# SCH_16b_ADC_DAC__2022-10-03.net
KiCad netlist of a schematic drawn in EasyEDA
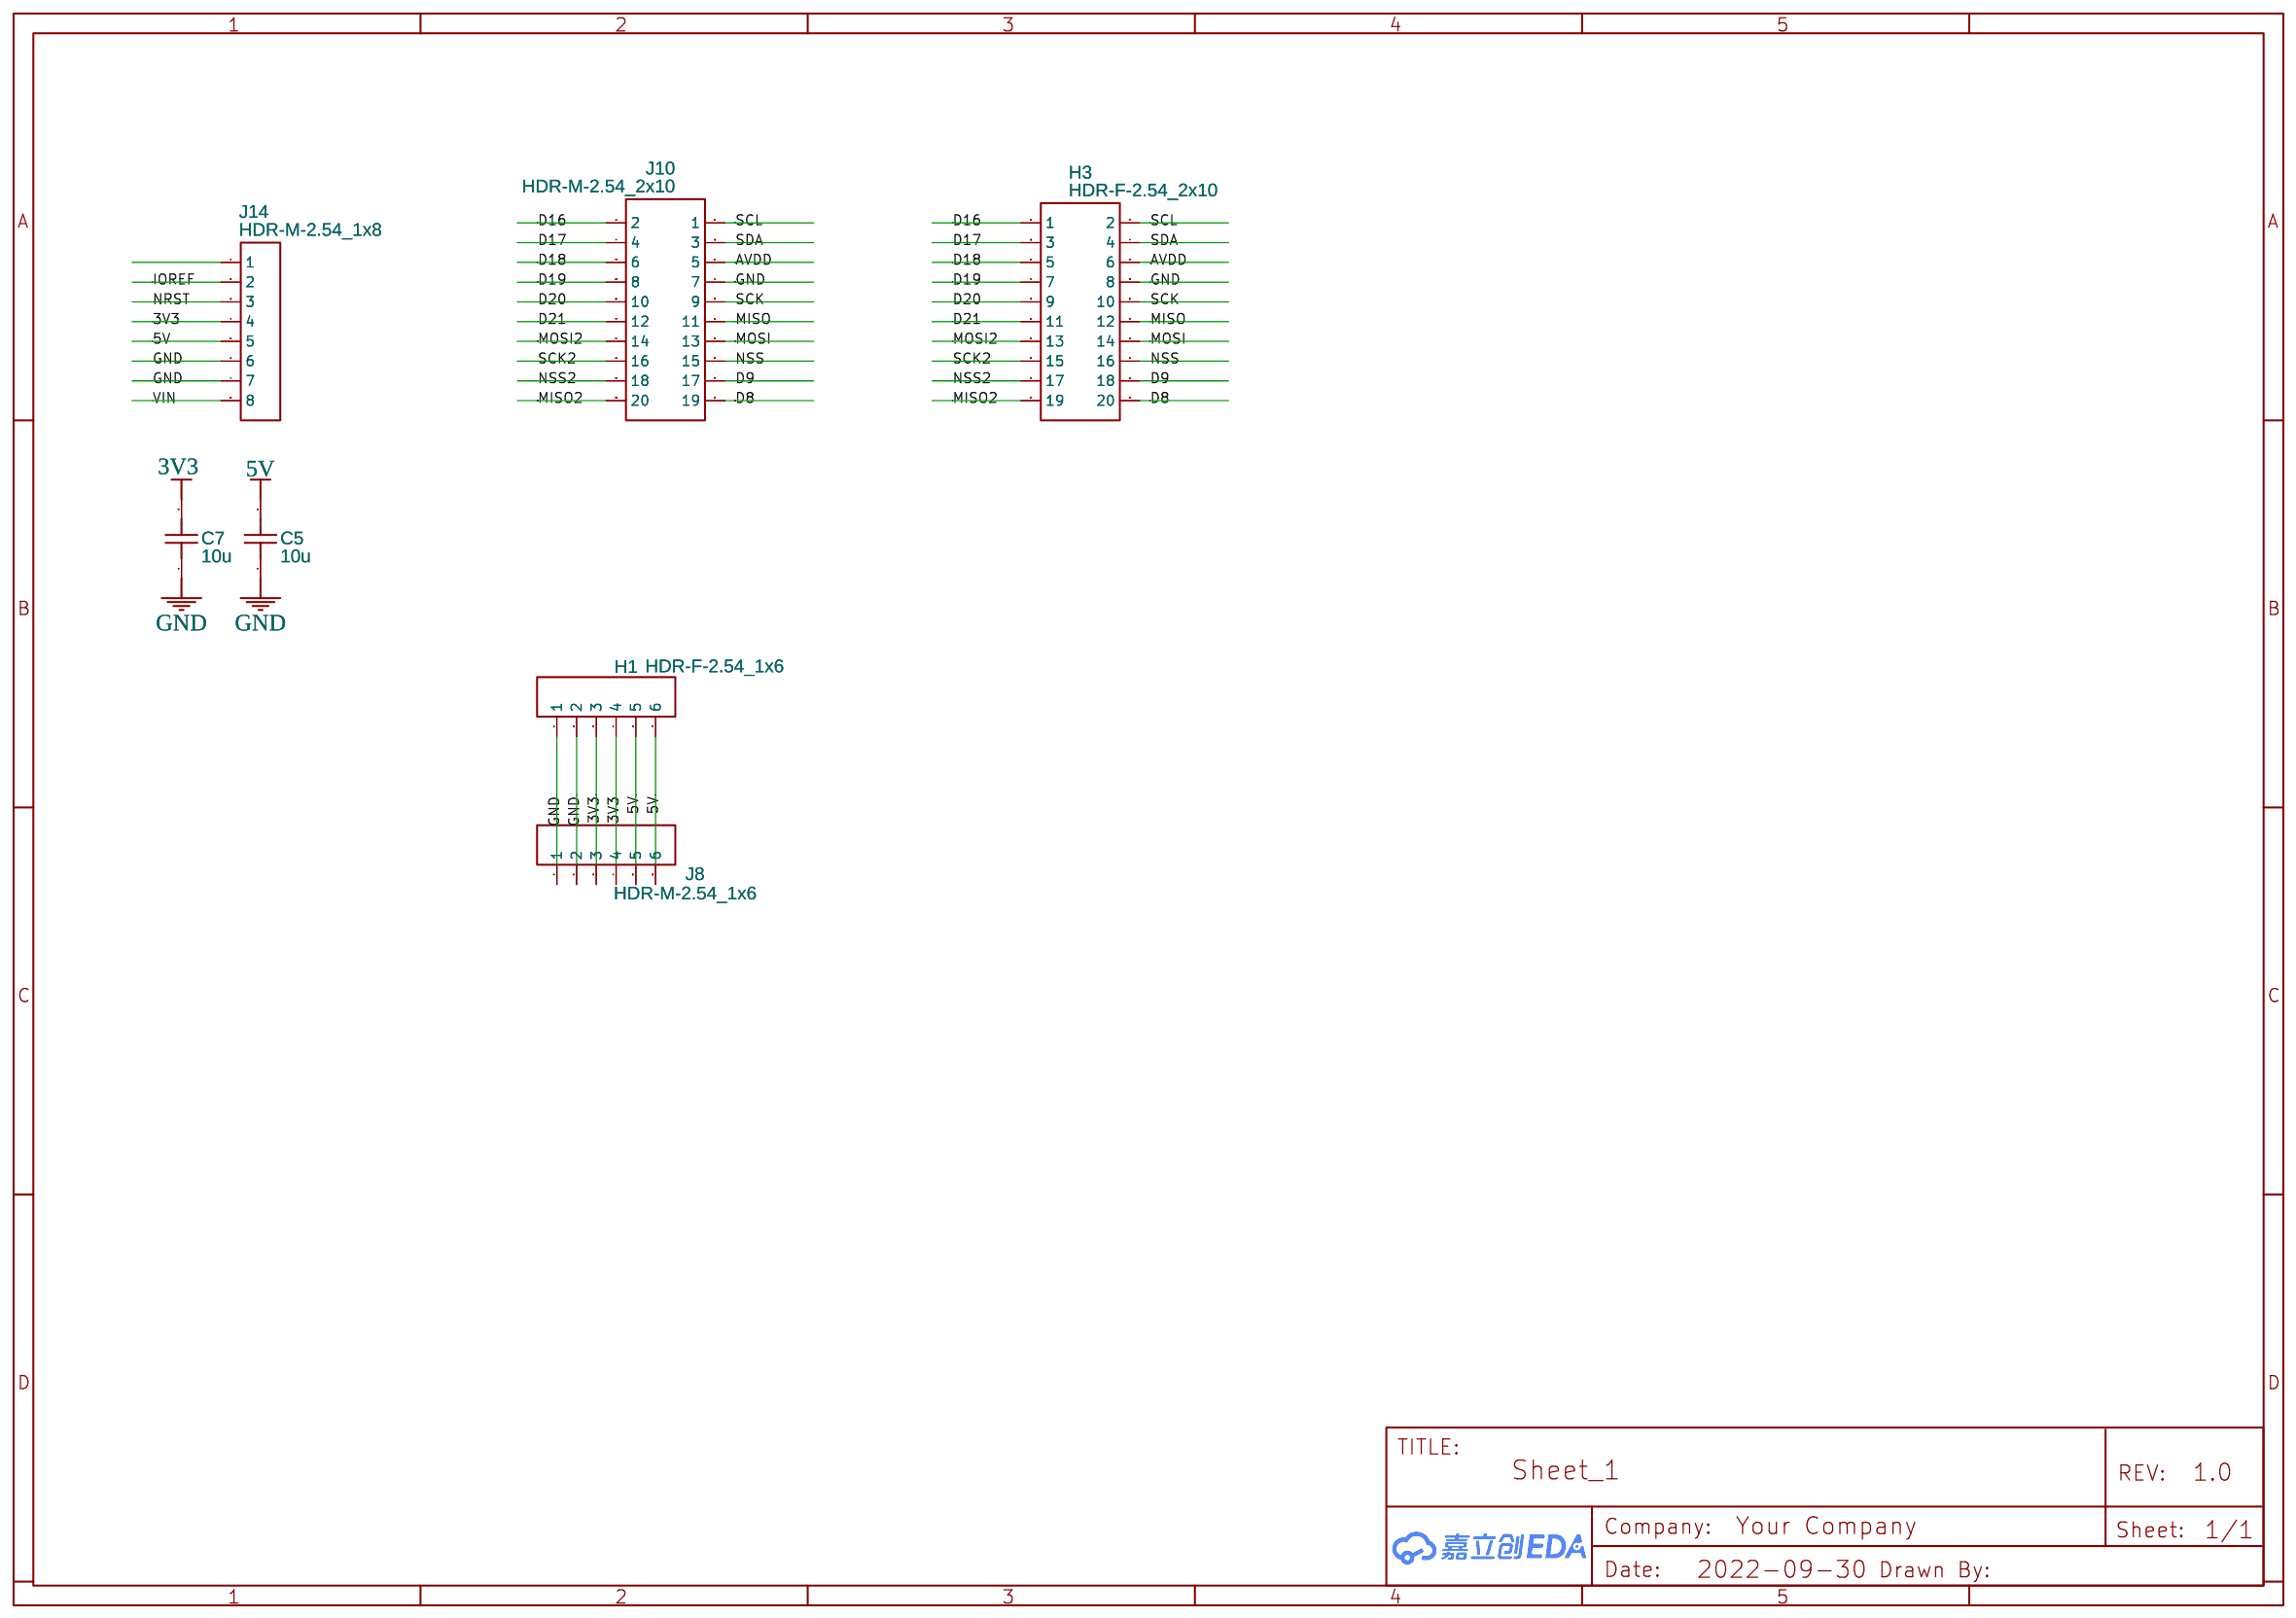
[diagram p0: 连接器]
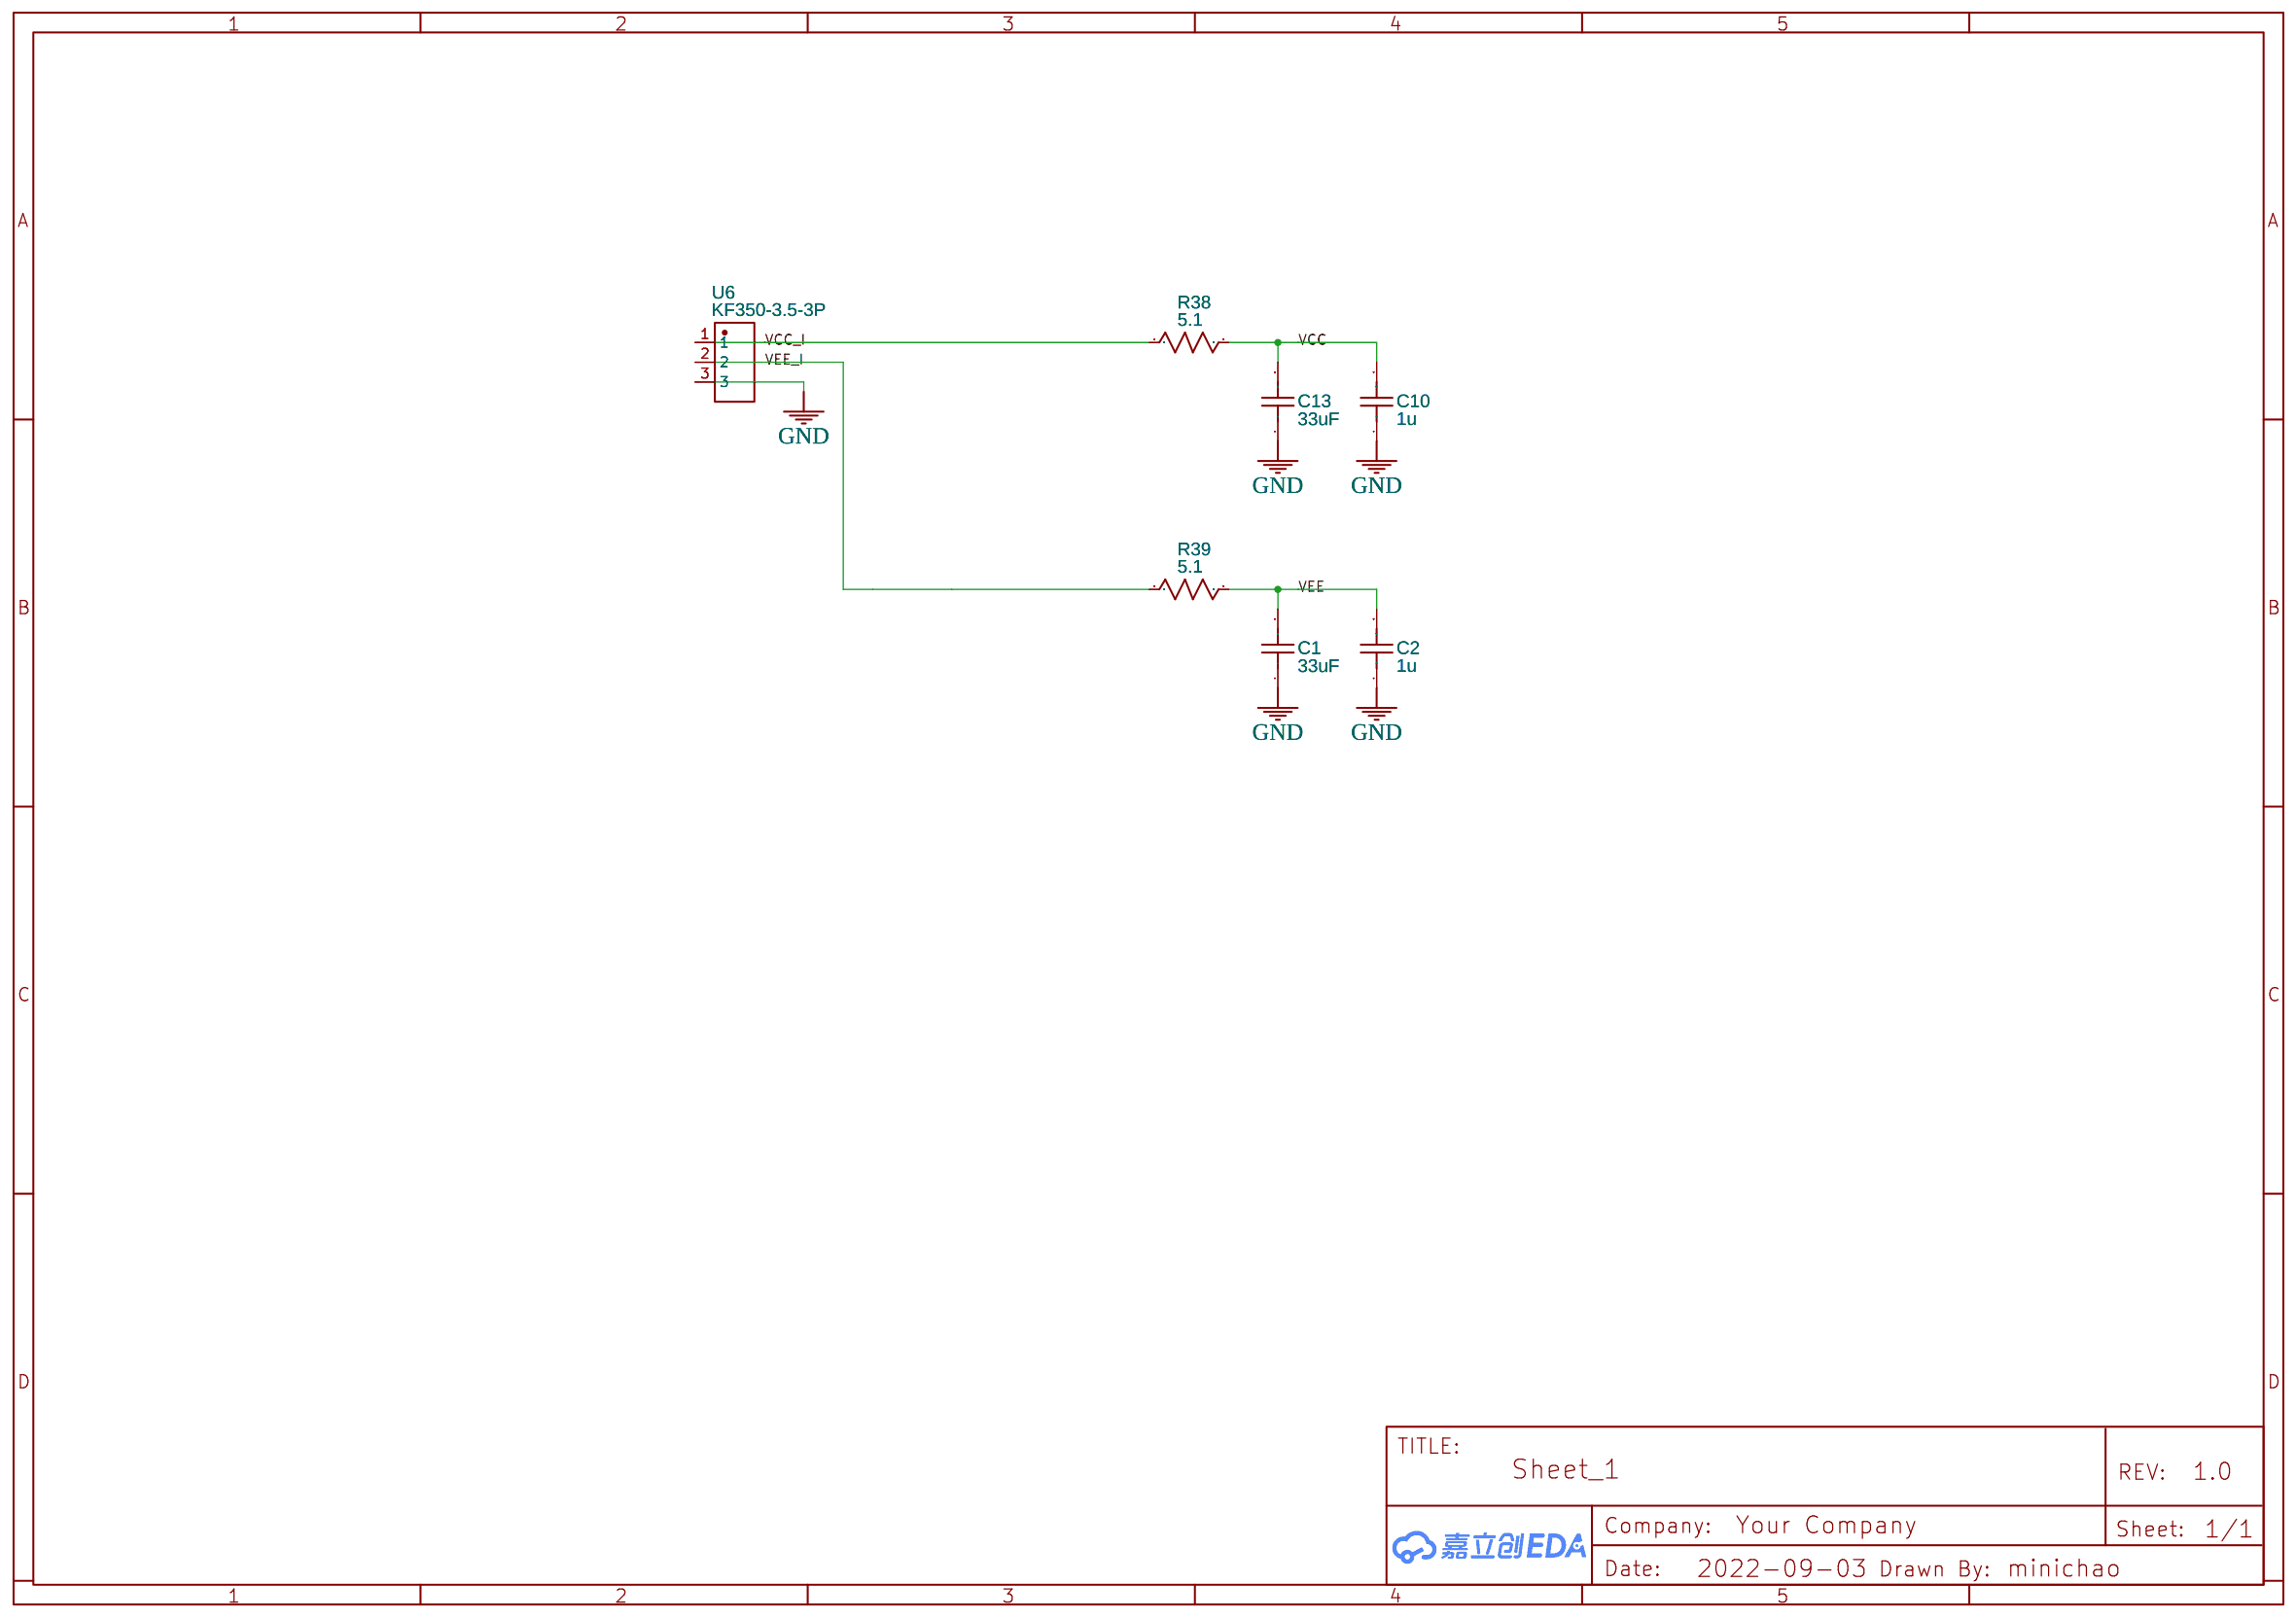
[diagram p1: 电源]
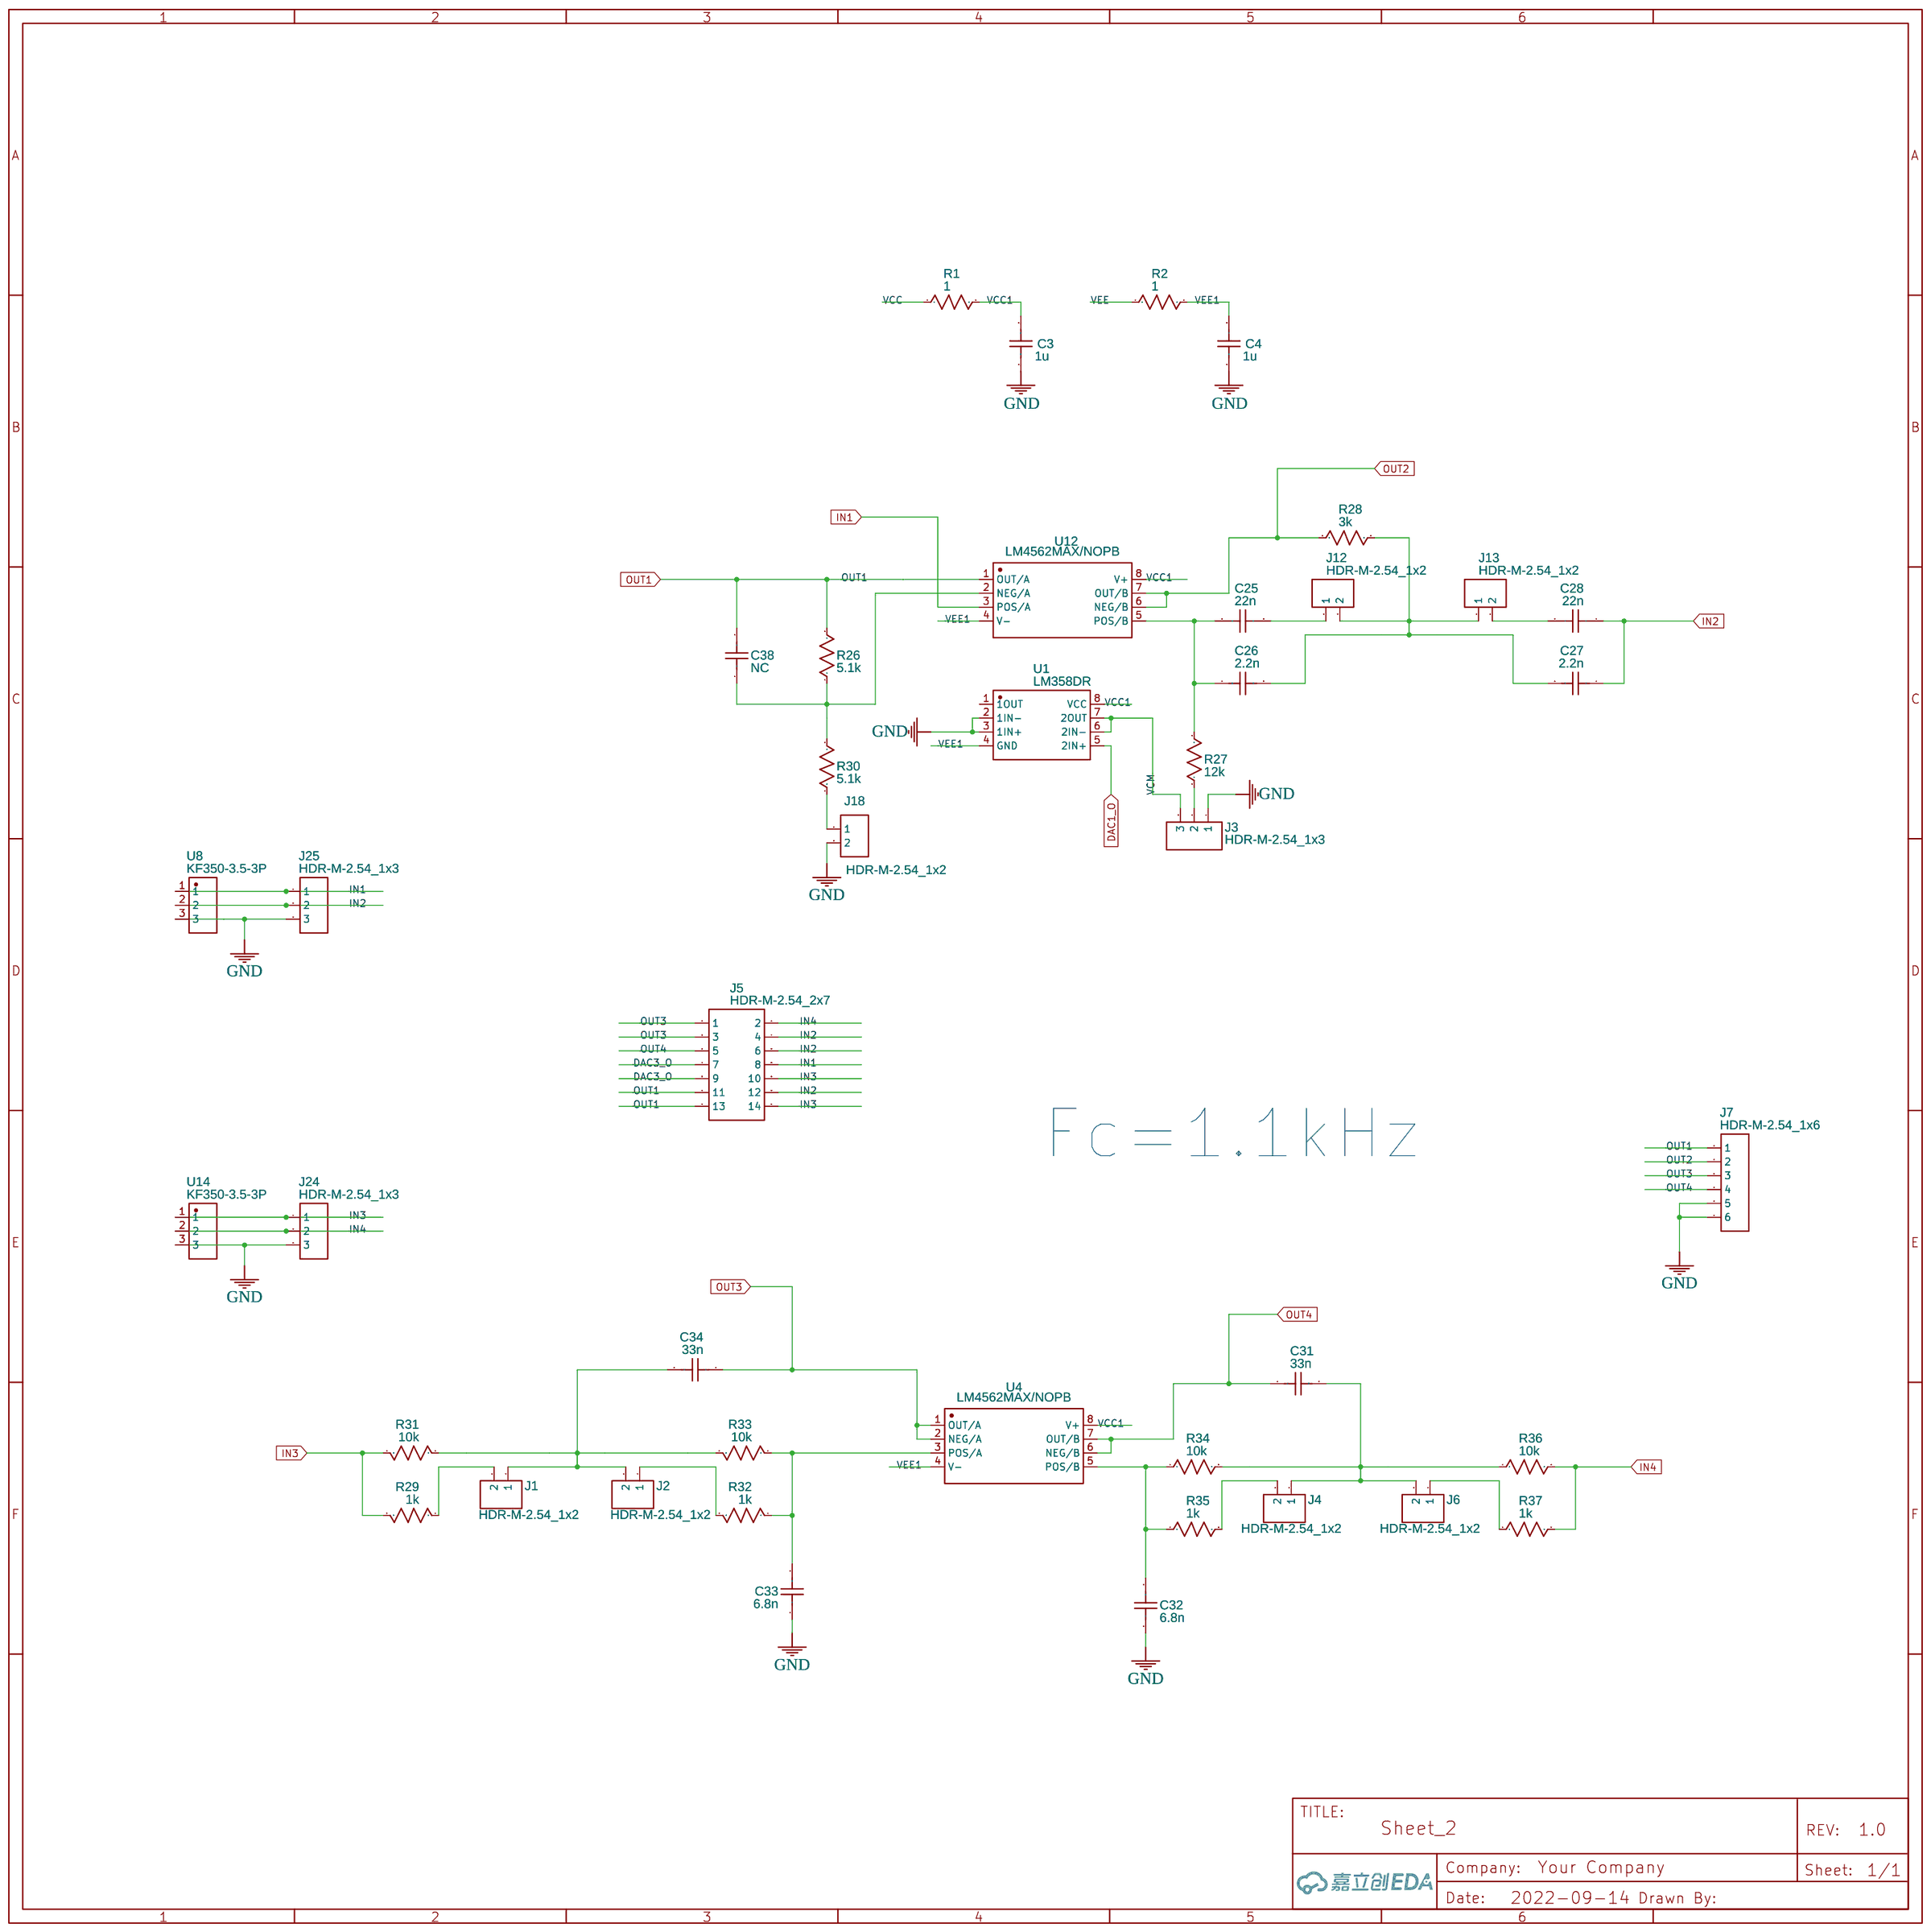
[diagram p2: 有源滤波器]
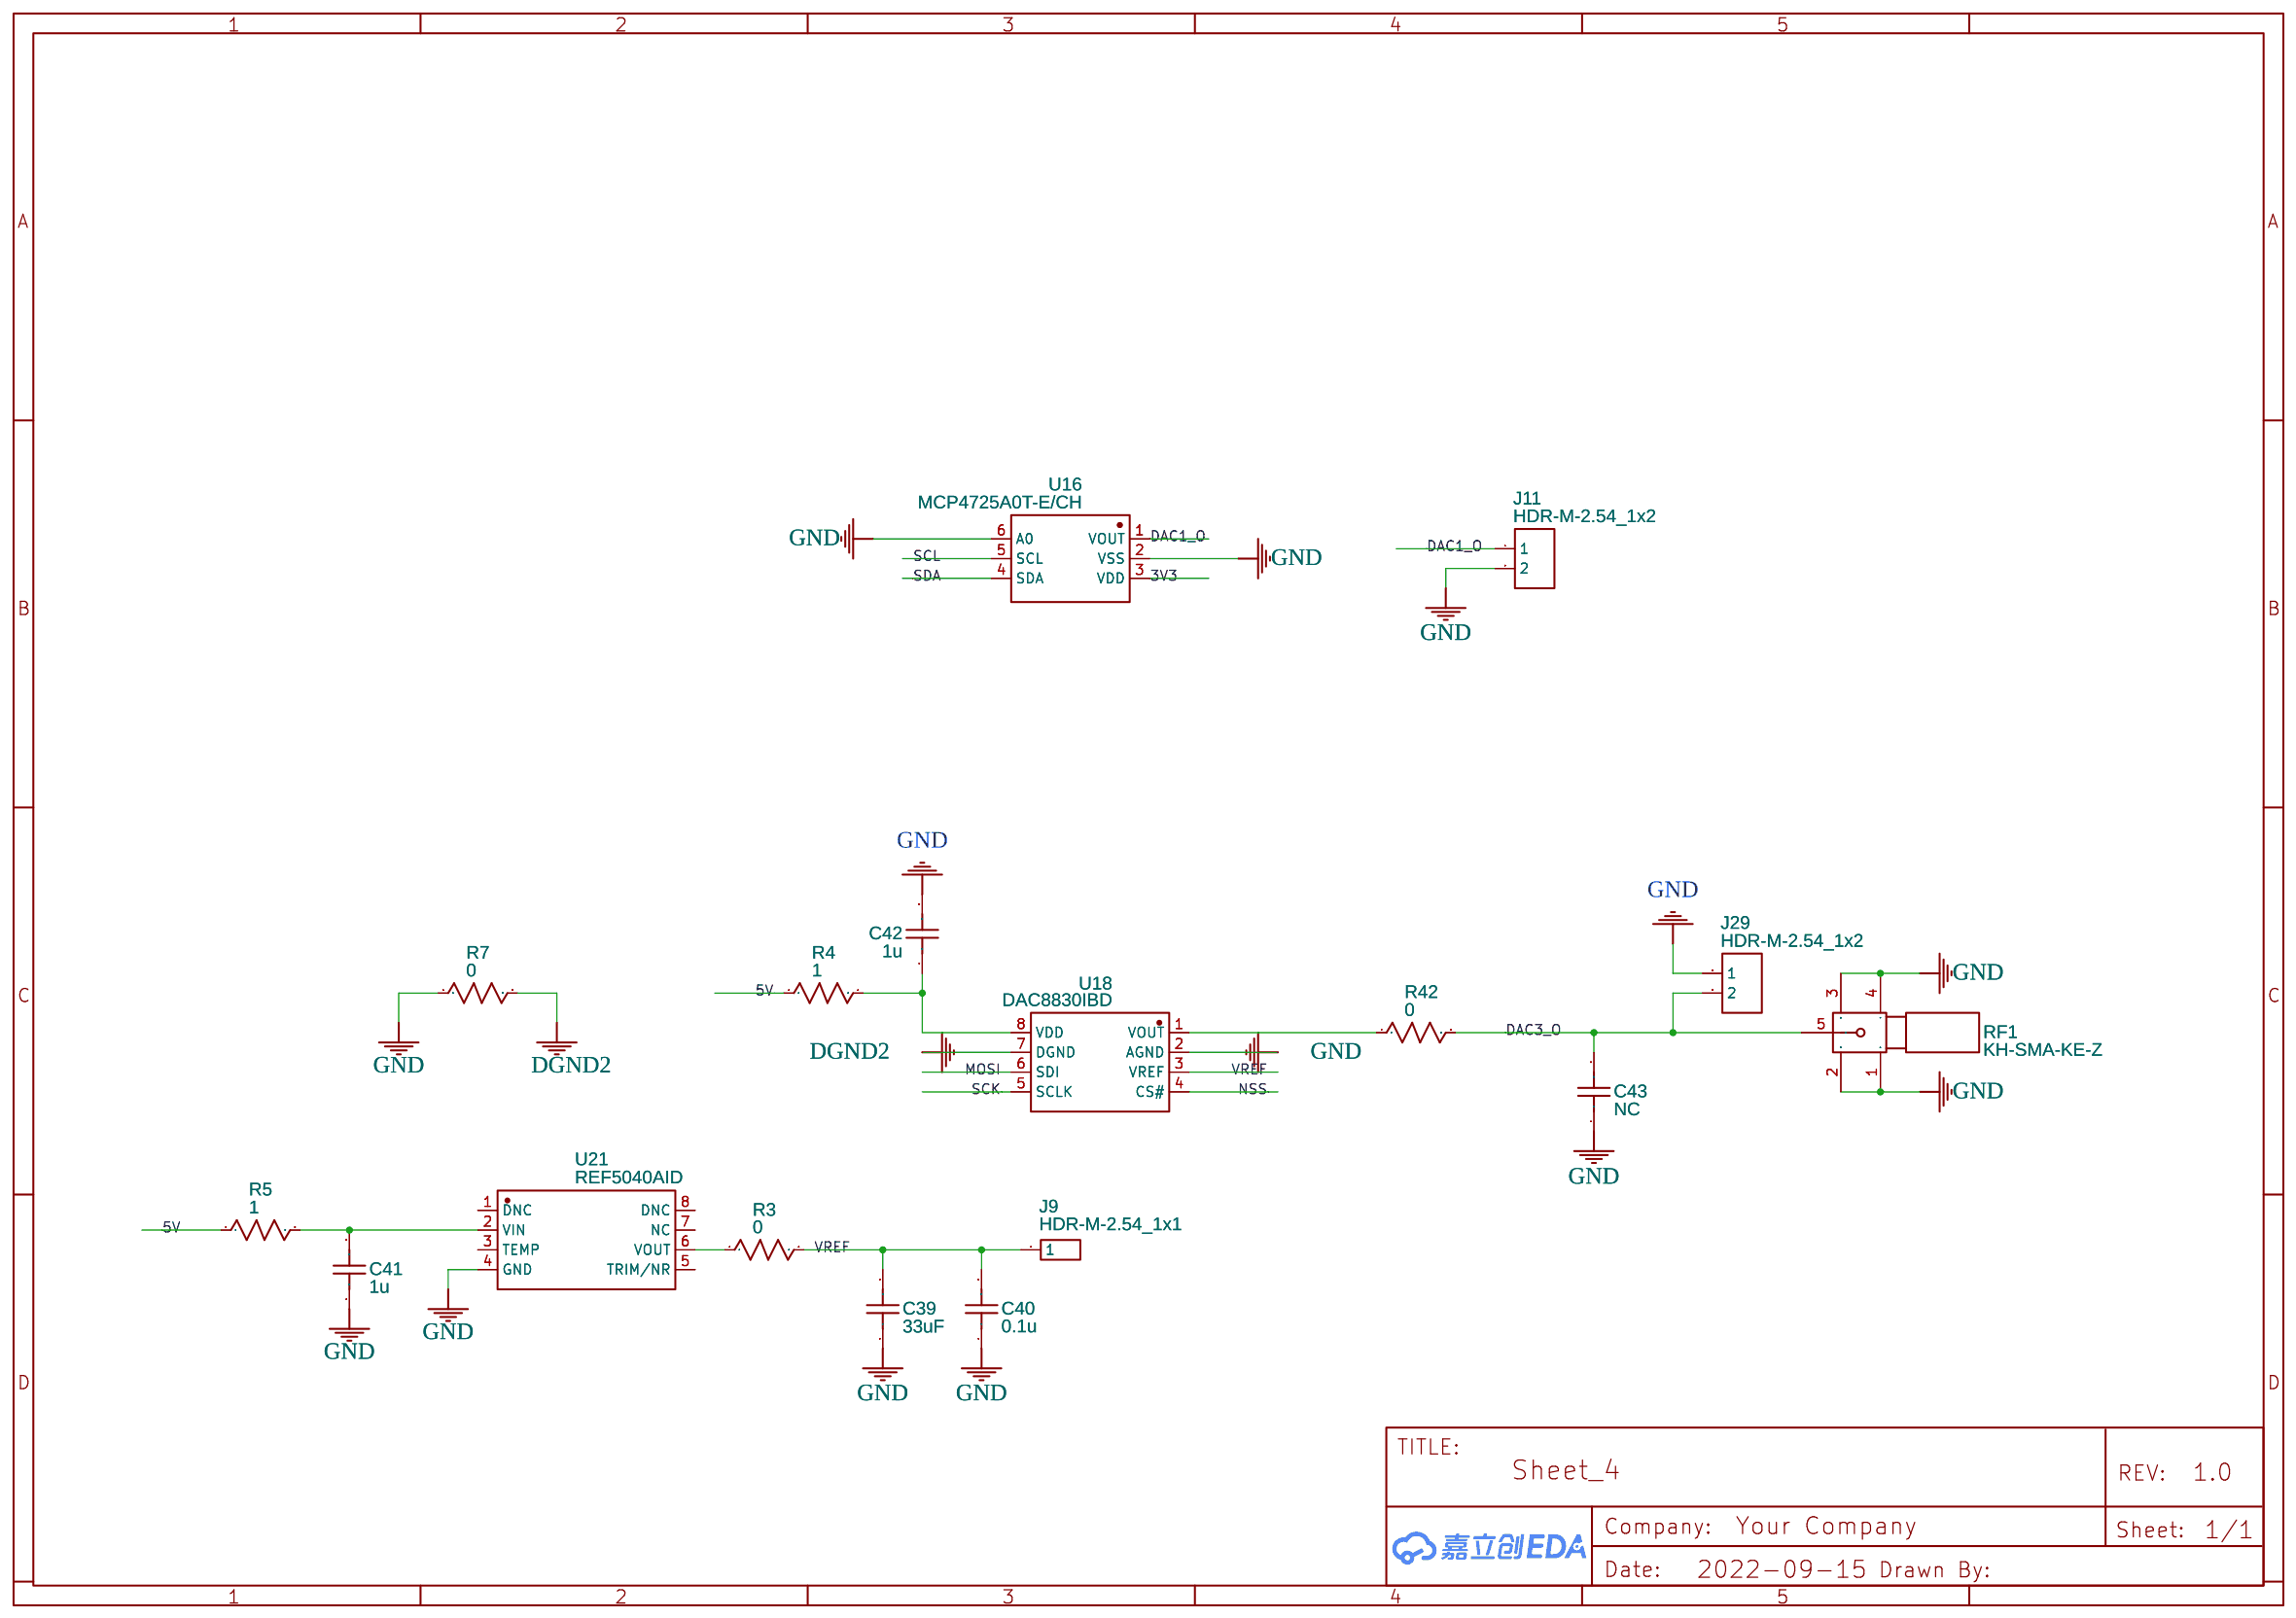
[diagram p3: dac与逻辑电路]
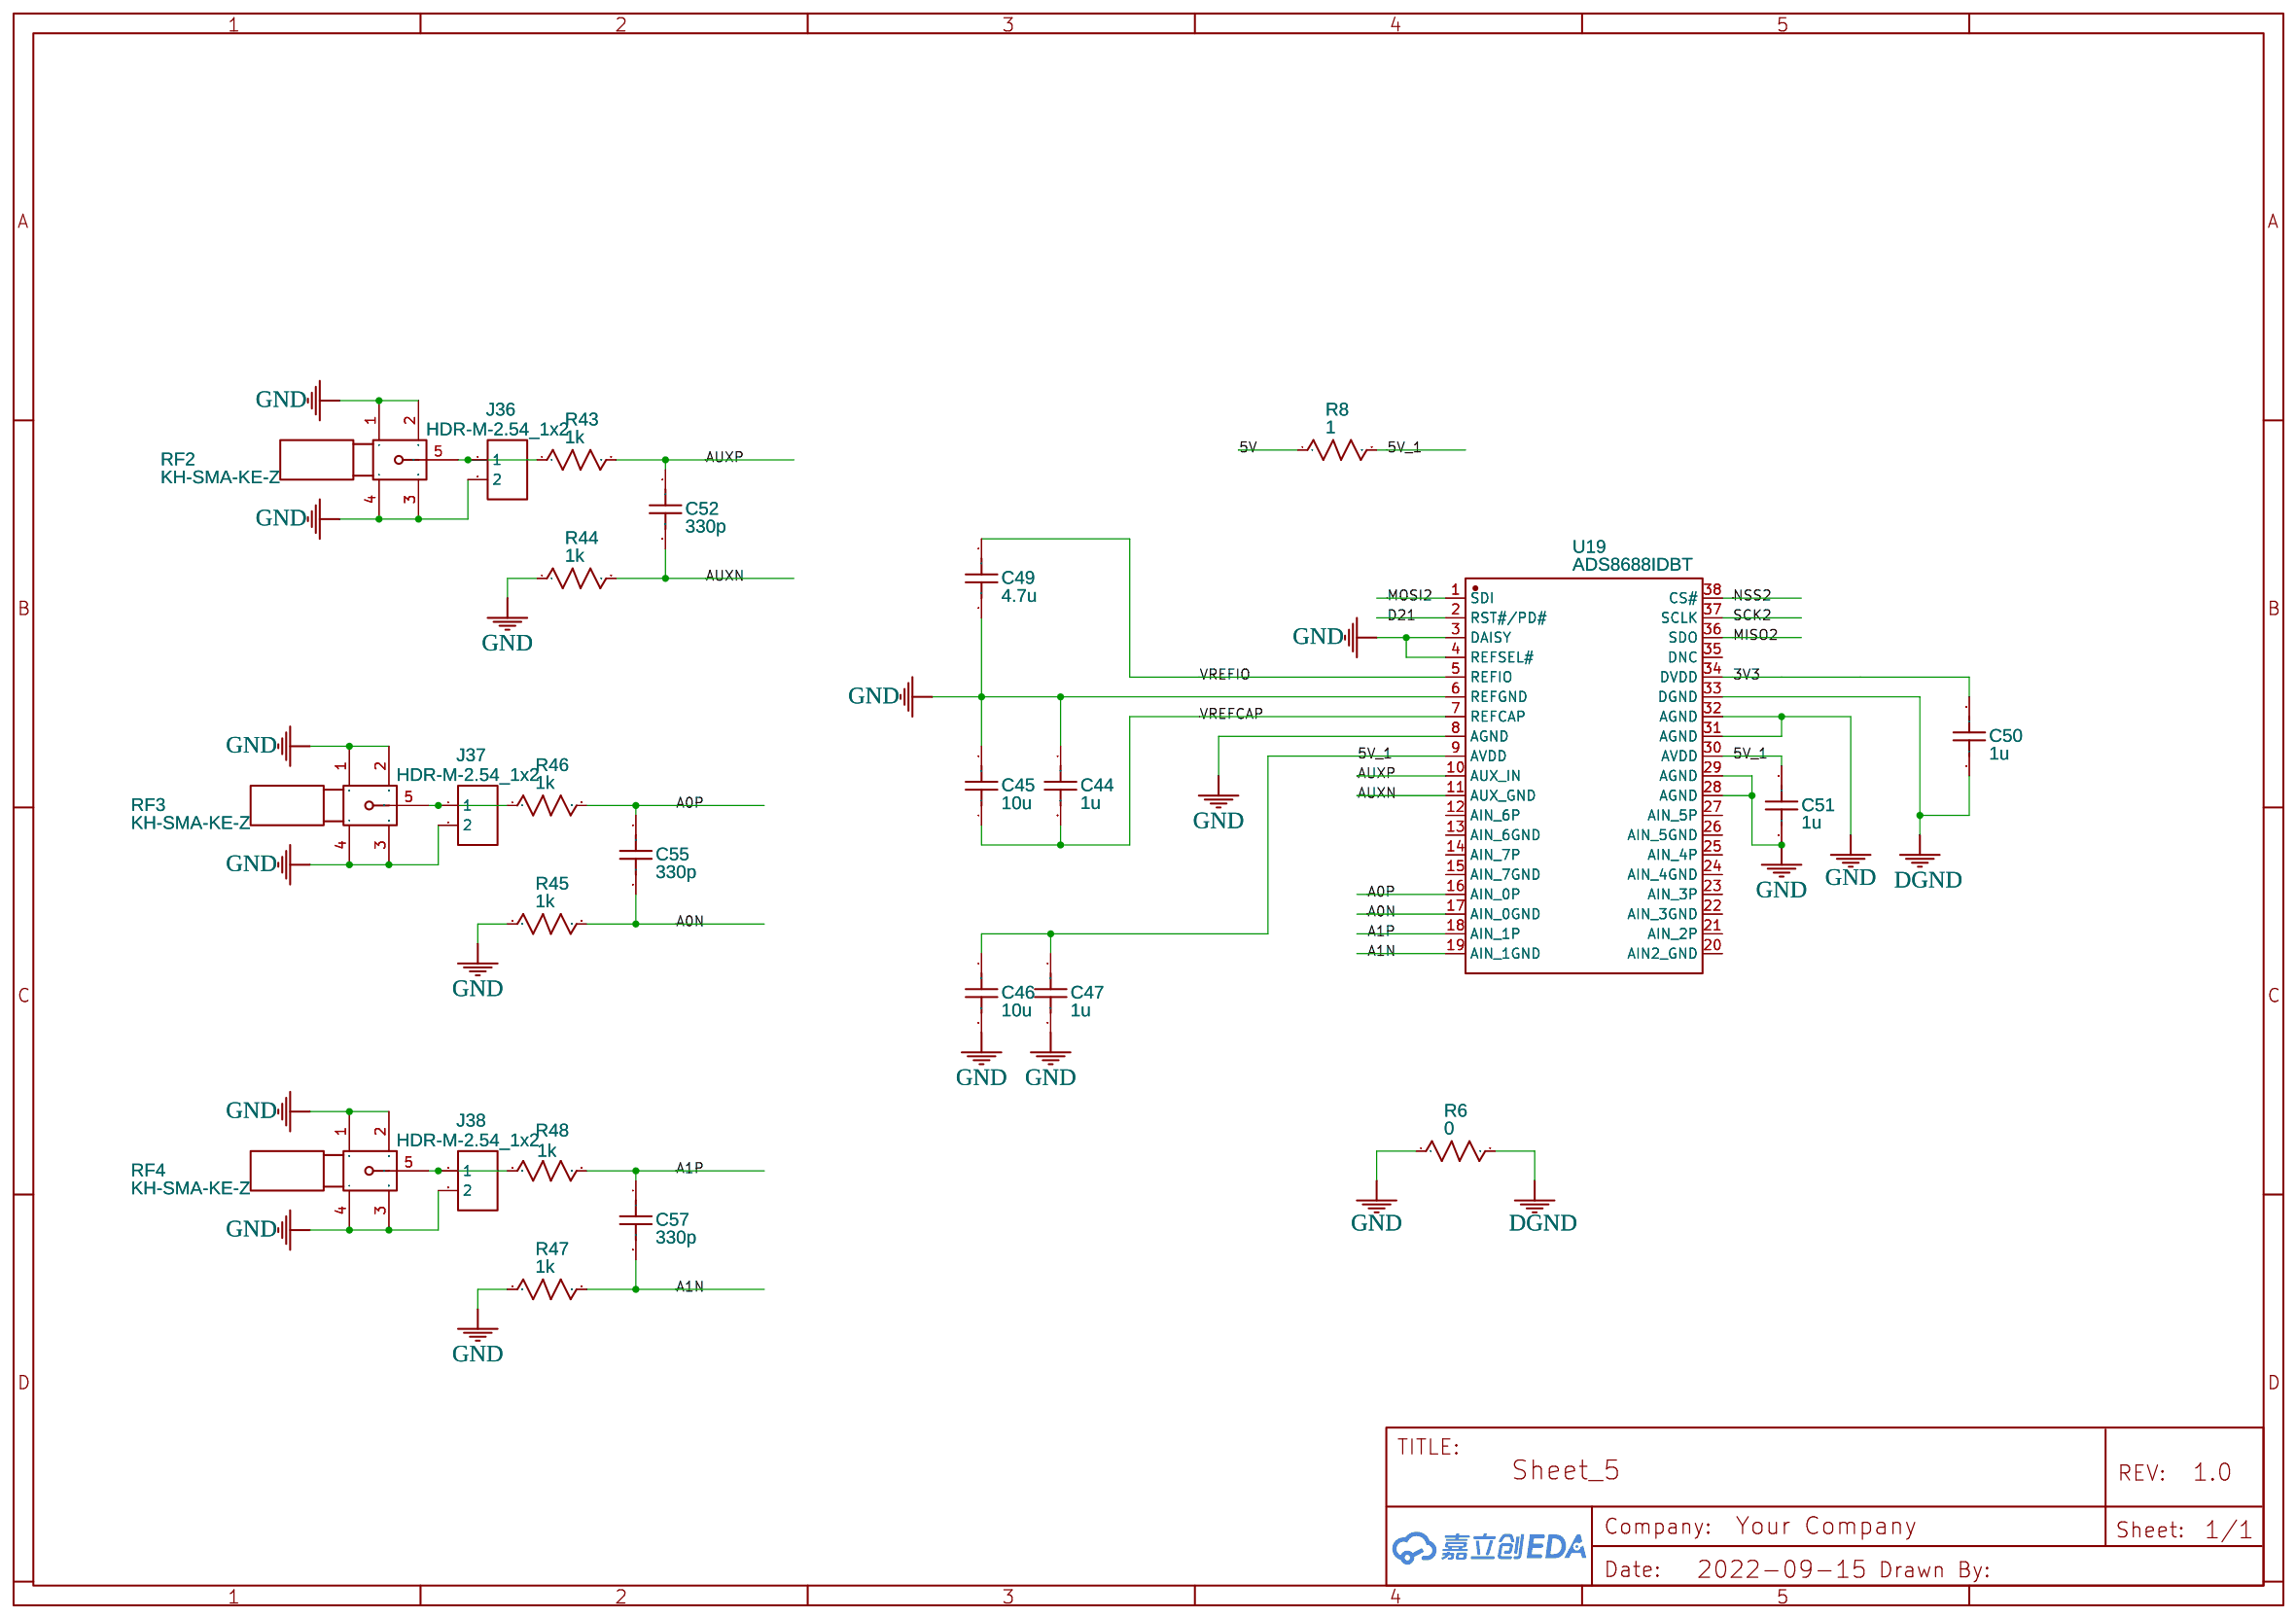
[diagram p4: adc]

(export (version "E")
  (design (tool "Eeschema 10.0.6"))
  (components
    (comp (ref "C5")
      (value "10u")
      (fields
        (field (name "BOM_Manufacturer Part") "0805B105M500NT")
        (field (name "BOM_Supplier Part") "C2913555")
      )
      (libsource (lib "") (part "C_0805_US"))
    )
    (comp (ref "C7")
      (value "10u")
      (fields
        (field (name "BOM_Manufacturer Part") "0805B105M500NT")
        (field (name "BOM_Supplier Part") "C2913555")
      )
      (libsource (lib "") (part "C_0805_US"))
    )
    (comp (ref "H1")
      (value "HDR-F-2.54_1x6")
      (fields (field (name "BOM_Supplier Part") "C40877"))
      (libsource (lib "") (part "HDR-F-2.54_1x6"))
    )
    (comp (ref "H3")
      (value "HDR-F-2.54_2x10")
      (fields (field (name "BOM_Supplier Part") "C30867"))
      (libsource (lib "") (part "HDR-F-2.54_2x10"))
    )
    (comp (ref "J8")
      (value "HDR-M-2.54_1x6")
      (fields (field (name "BOM_Supplier Part") "C190819"))
      (libsource (lib "") (part "HDR-M-2.54_1x6"))
    )
    (comp (ref "J10")
      (value "HDR-M-2.54_2x10")
      (fields (field (name "BOM_Supplier Part") "C124359"))
      (libsource (lib "") (part "HDR-M-2.54_2x10"))
    )
    (comp (ref "J14")
      (value "HDR-M-2.54_1x8")
      (fields (field (name "BOM_Supplier Part") "C190820"))
      (libsource (lib "") (part "HDR-M-2.54_1x8"))
    )
    (comp (ref "C1")
      (value "33uF")
      (fields
        (field (name "BOM_Manufacturer Part") "C4532X5R1C336MT000N")
        (field (name "BOM_Supplier Part") "C338113")
      )
      (libsource (lib "") (part "C4532X5R1C336MT000N"))
    )
    (comp (ref "C2") (value "1u") (libsource (lib "") (part "C_0805_US")))
    (comp (ref "C10") (value "1u") (libsource (lib "") (part "C_0805_US")))
    (comp (ref "C13")
      (value "33uF")
      (fields
        (field (name "BOM_Manufacturer Part") "C4532X5R1C336MT000N")
        (field (name "BOM_Supplier Part") "C338113")
      )
      (libsource (lib "") (part "C4532X5R1C336MT000N"))
    )
    (comp (ref "R38") (value "5.1") (libsource (lib "") (part "R_0805_US")))
    (comp (ref "R39") (value "5.1") (libsource (lib "") (part "R_0805_US")))
    (comp (ref "U6")
      (value "KF350-3.5-3P")
      (fields (field (name "BOM_Supplier Part") "C474893"))
      (libsource (lib "") (part "KF350-3.5-3P"))
    )
    (comp (ref "C3") (value "1u") (libsource (lib "") (part "C_0805_US_2")))
    (comp (ref "C4") (value "1u") (libsource (lib "") (part "C_0805_US_2")))
    (comp (ref "C25") (value "22n") (libsource (lib "") (part "C_0805_US_3")))
    (comp (ref "C26") (value "2.2n") (libsource (lib "") (part "C_0805_US_3")))
    (comp (ref "C27") (value "2.2n") (libsource (lib "") (part "C_0805_US")))
    (comp (ref "C28") (value "22n") (libsource (lib "") (part "C_0805_US")))
    (comp (ref "C31") (value "33n") (libsource (lib "") (part "C_0805_US_3")))
    (comp (ref "C32") (value "6.8n") (libsource (lib "") (part "C_0805_US_2")))
    (comp (ref "C33") (value "6.8n") (libsource (lib "") (part "C_0805_US_1")))
    (comp (ref "C34") (value "33n") (libsource (lib "") (part "C_0805_US")))
    (comp (ref "C38") (value "NC") (libsource (lib "") (part "C_0805_US_2")))
    (comp (ref "J1")
      (value "HDR-M-2.54_1x2")
      (fields (field (name "BOM_Supplier Part") "C124375"))
      (libsource (lib "") (part "HDR-M-2.54_1x2_1"))
    )
    (comp (ref "J2")
      (value "HDR-M-2.54_1x2")
      (fields (field (name "BOM_Supplier Part") "C124375"))
      (libsource (lib "") (part "HDR-M-2.54_1x2_1"))
    )
    (comp (ref "J3")
      (value "HDR-M-2.54_1x3")
      (fields (field (name "BOM_Supplier Part") "C180248"))
      (libsource (lib "") (part "HDR-M-2.54_1x3"))
    )
    (comp (ref "J4")
      (value "HDR-M-2.54_1x2")
      (fields (field (name "BOM_Supplier Part") "C124375"))
      (libsource (lib "") (part "HDR-M-2.54_1x2_1"))
    )
    (comp (ref "J5")
      (value "HDR-M-2.54_2x7")
      (fields (field (name "BOM_Supplier Part") "C71397"))
      (libsource (lib "") (part "HDR-M-2.54_2x7"))
    )
    (comp (ref "J6")
      (value "HDR-M-2.54_1x2")
      (fields (field (name "BOM_Supplier Part") "C124375"))
      (libsource (lib "") (part "HDR-M-2.54_1x2_1"))
    )
    (comp (ref "J7")
      (value "HDR-M-2.54_1x6")
      (fields (field (name "BOM_Supplier Part") "C190819"))
      (libsource (lib "") (part "HDR-M-2.54_1x6"))
    )
    (comp (ref "J12")
      (value "HDR-M-2.54_1x2")
      (fields (field (name "BOM_Supplier Part") "C124375"))
      (libsource (lib "") (part "HDR-M-2.54_1x2"))
    )
    (comp (ref "J13")
      (value "HDR-M-2.54_1x2")
      (fields (field (name "BOM_Supplier Part") "C124375"))
      (libsource (lib "") (part "HDR-M-2.54_1x2"))
    )
    (comp (ref "J18")
      (value "HDR-M-2.54_1x2")
      (fields (field (name "BOM_Supplier Part") "C124375"))
      (libsource (lib "") (part "HDR-M-2.54_1x2_2"))
    )
    (comp (ref "J24")
      (value "HDR-M-2.54_1x3")
      (fields (field (name "BOM_Supplier Part") "C180248"))
      (libsource (lib "") (part "HDR-M-2.54_1x3_1"))
    )
    (comp (ref "J25")
      (value "HDR-M-2.54_1x3")
      (fields (field (name "BOM_Supplier Part") "C180248"))
      (libsource (lib "") (part "HDR-M-2.54_1x3_1"))
    )
    (comp (ref "R1") (value "1") (libsource (lib "") (part "R_0805_US_1")))
    (comp (ref "R2") (value "1") (libsource (lib "") (part "R_0805_US_1")))
    (comp (ref "R26") (value "5.1k") (libsource (lib "") (part "R_0805_US")))
    (comp (ref "R27") (value "12k") (libsource (lib "") (part "R_0805_US")))
    (comp (ref "R28") (value "3k") (libsource (lib "") (part "R_0805_US_1")))
    (comp (ref "R29") (value "1k") (libsource (lib "") (part "R_0805_US_2")))
    (comp (ref "R30") (value "5.1k") (libsource (lib "") (part "R_0805_US")))
    (comp (ref "R31") (value "10k") (libsource (lib "") (part "R_0805_US_2")))
    (comp (ref "R32") (value "1k") (libsource (lib "") (part "R_0805_US_2")))
    (comp (ref "R33") (value "10k") (libsource (lib "") (part "R_0805_US_2")))
    (comp (ref "R34") (value "10k") (libsource (lib "") (part "R_0805_US_1")))
    (comp (ref "R35") (value "1k") (libsource (lib "") (part "R_0805_US_1")))
    (comp (ref "R36") (value "10k") (libsource (lib "") (part "R_0805_US_1")))
    (comp (ref "R37") (value "1k") (libsource (lib "") (part "R_0805_US_1")))
    (comp (ref "U1")
      (value "LM358DR")
      (fields (field (name "BOM_Supplier Part") "C5423"))
      (libsource (lib "") (part "LM358DR"))
    )
    (comp (ref "U4")
      (value "LM4562MAX/NOPB")
      (fields (field (name "BOM_Supplier Part") "C57367"))
      (libsource (lib "") (part "LM4562MAX/NOPB"))
    )
    (comp (ref "U8")
      (value "KF350-3.5-3P")
      (fields (field (name "BOM_Supplier Part") "C474893"))
      (libsource (lib "") (part "KF350-3.5-3P"))
    )
    (comp (ref "U12")
      (value "LM4562MAX/NOPB")
      (fields (field (name "BOM_Supplier Part") "C57367"))
      (libsource (lib "") (part "LM4562MAX/NOPB"))
    )
    (comp (ref "U14")
      (value "KF350-3.5-3P")
      (fields (field (name "BOM_Supplier Part") "C474893"))
      (libsource (lib "") (part "KF350-3.5-3P"))
    )
    (comp (ref "C39")
      (value "33uF")
      (fields
        (field (name "BOM_Manufacturer Part") "C4532X5R1C336MT000N")
        (field (name "BOM_Supplier Part") "C338113")
      )
      (libsource (lib "") (part "C4532X5R1C336MT000N"))
    )
    (comp (ref "C40") (value "0.1u") (libsource (lib "") (part "C_0805_US_1")))
    (comp (ref "C41") (value "1u") (libsource (lib "") (part "C_0805_US_1")))
    (comp (ref "C42") (value "1u") (libsource (lib "") (part "C_0805_US")))
    (comp (ref "C43") (value "NC") (libsource (lib "") (part "C_0805_US_1")))
    (comp (ref "J9")
      (value "HDR-M-2.54_1x1")
      (fields (field (name "BOM_Supplier Part") "C81276"))
      (libsource (lib "") (part "HDR-M-2.54_1x1"))
    )
    (comp (ref "J11")
      (value "HDR-M-2.54_1x2")
      (fields (field (name "BOM_Supplier Part") "C124375"))
      (libsource (lib "") (part "HDR-M-2.54_1x2"))
    )
    (comp (ref "J29")
      (value "HDR-M-2.54_1x2")
      (fields (field (name "BOM_Supplier Part") "C124375"))
      (libsource (lib "") (part "HDR-M-2.54_1x2"))
    )
    (comp (ref "R3") (value "0") (libsource (lib "") (part "R_0805_US")))
    (comp (ref "R4") (value "1") (libsource (lib "") (part "R_0805_US")))
    (comp (ref "R5") (value "1") (libsource (lib "") (part "R_0805_US")))
    (comp (ref "R7") (value "0") (libsource (lib "") (part "R_0805_US")))
    (comp (ref "R42") (value "0") (libsource (lib "") (part "R_0805_US")))
    (comp (ref "RF1")
      (value "KH-SMA-KE-Z")
      (fields (field (name "BOM_Supplier Part") "C504007"))
      (libsource (lib "") (part "KH-SMA-KE-Z"))
    )
    (comp (ref "U16")
      (value "MCP4725A0T-E/CH")
      (fields (field (name "BOM_Supplier Part") "C144198"))
      (libsource (lib "") (part "MCP4725A0T-E/CH"))
    )
    (comp (ref "U18")
      (value "DAC8830IBD")
      (fields (field (name "BOM_Supplier Part") "C1554469"))
      (libsource (lib "") (part "DAC8830IBD"))
    )
    (comp (ref "U21")
      (value "REF5040AID")
      (fields (field (name "BOM_Supplier Part") "C1575304"))
      (libsource (lib "") (part "REF5040AID"))
    )
    (comp (ref "C44") (value "1u") (libsource (lib "") (part "C_0805_US")))
    (comp (ref "C45") (value "10u") (libsource (lib "") (part "C_0805_US_1")))
    (comp (ref "C46") (value "10u") (libsource (lib "") (part "C_0805_US")))
    (comp (ref "C47") (value "1u") (libsource (lib "") (part "C_0805_US")))
    (comp (ref "C49") (value "4.7u") (libsource (lib "") (part "C_0805_US_1")))
    (comp (ref "C50") (value "1u") (libsource (lib "") (part "C_0805_US_1")))
    (comp (ref "C51") (value "1u") (libsource (lib "") (part "C_0805_US_1")))
    (comp (ref "C52") (value "330p") (libsource (lib "") (part "C_0805_US")))
    (comp (ref "C55") (value "330p") (libsource (lib "") (part "C_0805_US")))
    (comp (ref "C57") (value "330p") (libsource (lib "") (part "C_0805_US")))
    (comp (ref "J36")
      (value "HDR-M-2.54_1x2")
      (fields (field (name "BOM_Supplier Part") "C124375"))
      (libsource (lib "") (part "HDR-M-2.54_1x2"))
    )
    (comp (ref "J37")
      (value "HDR-M-2.54_1x2")
      (fields (field (name "BOM_Supplier Part") "C124375"))
      (libsource (lib "") (part "HDR-M-2.54_1x2"))
    )
    (comp (ref "J38")
      (value "HDR-M-2.54_1x2")
      (fields (field (name "BOM_Supplier Part") "C124375"))
      (libsource (lib "") (part "HDR-M-2.54_1x2"))
    )
    (comp (ref "R6") (value "0") (libsource (lib "") (part "R_0805_US")))
    (comp (ref "R8") (value "1") (libsource (lib "") (part "R_0805_US")))
    (comp (ref "R43") (value "1k") (libsource (lib "") (part "R_0805_US")))
    (comp (ref "R44") (value "1k") (libsource (lib "") (part "R_0805_US")))
    (comp (ref "R45") (value "1k") (libsource (lib "") (part "R_0805_US")))
    (comp (ref "R46") (value "1k") (libsource (lib "") (part "R_0805_US")))
    (comp (ref "R47") (value "1k") (libsource (lib "") (part "R_0805_US")))
    (comp (ref "R48") (value "1k") (libsource (lib "") (part "R_0805_US")))
    (comp (ref "RF2")
      (value "KH-SMA-KE-Z")
      (fields (field (name "BOM_Supplier Part") "C504007"))
      (libsource (lib "") (part "KH-SMA-KE-Z"))
    )
    (comp (ref "RF3")
      (value "KH-SMA-KE-Z")
      (fields (field (name "BOM_Supplier Part") "C504007"))
      (libsource (lib "") (part "KH-SMA-KE-Z"))
    )
    (comp (ref "RF4")
      (value "KH-SMA-KE-Z")
      (fields (field (name "BOM_Supplier Part") "C504007"))
      (libsource (lib "") (part "KH-SMA-KE-Z"))
    )
    (comp (ref "U19")
      (value "ADS8688IDBT")
      (fields (field (name "BOM_Supplier Part") "C1542682"))
      (libsource (lib "") (part "ADS8688IDBT"))
    )
  )
  (nets
    (net (code "1") (name "3V3") (class "Default")
      (node (ref "C50") (pin "2") (pinfunction "2_2") (pintype "unspecified"))
      (node (ref "C7") (pin "2") (pinfunction "2_2") (pintype "unspecified"))
      (node (ref "H1") (pin "3") (pinfunction "3_3") (pintype "input"))
      (node (ref "H1") (pin "4") (pinfunction "4_4") (pintype "input"))
      (node (ref "J14") (pin "4") (pinfunction "4_4") (pintype "unspecified"))
      (node (ref "J8") (pin "3") (pinfunction "3_3") (pintype "input"))
      (node (ref "J8") (pin "4") (pinfunction "4_4") (pintype "input"))
      (node (ref "U16") (pin "3") (pinfunction "VDD_3") (pintype "unspecified"))
      (node (ref "U19") (pin "34") (pinfunction "DVDD_34") (pintype "unspecified"))
    )
    (net (code "2") (name "5V") (class "Default")
      (node (ref "C5") (pin "2") (pinfunction "2_2") (pintype "unspecified"))
      (node (ref "H1") (pin "5") (pinfunction "5_5") (pintype "input"))
      (node (ref "H1") (pin "6") (pinfunction "6_6") (pintype "input"))
      (node (ref "J14") (pin "5") (pinfunction "5_5") (pintype "unspecified"))
      (node (ref "J8") (pin "5") (pinfunction "5_5") (pintype "input"))
      (node (ref "J8") (pin "6") (pinfunction "6_6") (pintype "input"))
      (node (ref "R4") (pin "1") (pinfunction "1_1") (pintype "unspecified"))
      (node (ref "R5") (pin "1") (pinfunction "1_1") (pintype "unspecified"))
      (node (ref "R8") (pin "1") (pinfunction "1_1") (pintype "unspecified"))
    )
    (net (code "3") (name "5V_1") (class "Default")
      (node (ref "C46") (pin "1") (pinfunction "1_1") (pintype "unspecified"))
      (node (ref "C47") (pin "1") (pinfunction "1_1") (pintype "unspecified"))
      (node (ref "C51") (pin "2") (pinfunction "2_2") (pintype "unspecified"))
      (node (ref "R8") (pin "2") (pinfunction "2_2") (pintype "unspecified"))
      (node (ref "U19") (pin "30") (pinfunction "AVDD_30") (pintype "unspecified"))
      (node (ref "U19") (pin "9") (pinfunction "AVDD_9") (pintype "unspecified"))
    )
    (net (code "4") (name "A0N") (class "Default")
      (node (ref "C55") (pin "2") (pinfunction "2_2") (pintype "unspecified"))
      (node (ref "R45") (pin "2") (pinfunction "2_2") (pintype "unspecified"))
      (node (ref "U19") (pin "17") (pinfunction "AIN_0GND_17") (pintype "unspecified"))
    )
    (net (code "5") (name "A0P") (class "Default")
      (node (ref "C55") (pin "1") (pinfunction "1_1") (pintype "unspecified"))
      (node (ref "R46") (pin "2") (pinfunction "2_2") (pintype "unspecified"))
      (node (ref "U19") (pin "16") (pinfunction "AIN_0P_16") (pintype "unspecified"))
    )
    (net (code "6") (name "A1N") (class "Default")
      (node (ref "C57") (pin "2") (pinfunction "2_2") (pintype "unspecified"))
      (node (ref "R47") (pin "2") (pinfunction "2_2") (pintype "unspecified"))
      (node (ref "U19") (pin "19") (pinfunction "AIN_1GND_19") (pintype "unspecified"))
    )
    (net (code "7") (name "A1P") (class "Default")
      (node (ref "C57") (pin "1") (pinfunction "1_1") (pintype "unspecified"))
      (node (ref "R48") (pin "2") (pinfunction "2_2") (pintype "unspecified"))
      (node (ref "U19") (pin "18") (pinfunction "AIN_1P_18") (pintype "unspecified"))
    )
    (net (code "8") (name "AUXN") (class "Default")
      (node (ref "C52") (pin "2") (pinfunction "2_2") (pintype "unspecified"))
      (node (ref "R44") (pin "2") (pinfunction "2_2") (pintype "unspecified"))
      (node (ref "U19") (pin "11") (pinfunction "AUX_GND_11") (pintype "unspecified"))
    )
    (net (code "9") (name "AUXP") (class "Default")
      (node (ref "C52") (pin "1") (pinfunction "1_1") (pintype "unspecified"))
      (node (ref "R43") (pin "2") (pinfunction "2_2") (pintype "unspecified"))
      (node (ref "U19") (pin "10") (pinfunction "AUX_IN_10") (pintype "unspecified"))
    )
    (net (code "10") (name "AVDD") (class "Default")
      (node (ref "H3") (pin "6") (pinfunction "6_6") (pintype "input"))
      (node (ref "J10") (pin "5") (pinfunction "5_5") (pintype "unspecified"))
    )
    (net (code "11") (name "D8") (class "Default")
      (node (ref "H3") (pin "20") (pinfunction "20_20") (pintype "input"))
      (node (ref "J10") (pin "19") (pinfunction "19_19") (pintype "unspecified"))
    )
    (net (code "12") (name "D9") (class "Default")
      (node (ref "H3") (pin "18") (pinfunction "18_18") (pintype "input"))
      (node (ref "J10") (pin "17") (pinfunction "17_17") (pintype "unspecified"))
    )
    (net (code "13") (name "D16") (class "Default")
      (node (ref "H3") (pin "1") (pinfunction "1_1") (pintype "input"))
      (node (ref "J10") (pin "2") (pinfunction "2_2") (pintype "unspecified"))
    )
    (net (code "14") (name "D17") (class "Default")
      (node (ref "H3") (pin "3") (pinfunction "3_3") (pintype "input"))
      (node (ref "J10") (pin "4") (pinfunction "4_4") (pintype "unspecified"))
    )
    (net (code "15") (name "D18") (class "Default")
      (node (ref "H3") (pin "5") (pinfunction "5_5") (pintype "input"))
      (node (ref "J10") (pin "6") (pinfunction "6_6") (pintype "unspecified"))
    )
    (net (code "16") (name "D19") (class "Default")
      (node (ref "H3") (pin "7") (pinfunction "7_7") (pintype "input"))
      (node (ref "J10") (pin "8") (pinfunction "8_8") (pintype "unspecified"))
    )
    (net (code "17") (name "D20") (class "Default")
      (node (ref "H3") (pin "9") (pinfunction "9_9") (pintype "input"))
      (node (ref "J10") (pin "10") (pinfunction "10_10") (pintype "unspecified"))
    )
    (net (code "18") (name "D21") (class "Default")
      (node (ref "H3") (pin "11") (pinfunction "11_11") (pintype "input"))
      (node (ref "J10") (pin "12") (pinfunction "12_12") (pintype "unspecified"))
      (node (ref "U19") (pin "2") (pinfunction "RST#/PD#_2") (pintype "unspecified"))
    )
    (net (code "19") (name "DAC1_O") (class "Default")
      (node (ref "J11") (pin "1") (pinfunction "1_1") (pintype "unspecified"))
      (node (ref "U1") (pin "5") (pinfunction "2IN+_5") (pintype "unspecified"))
      (node (ref "U16") (pin "1") (pinfunction "VOUT_1") (pintype "unspecified"))
    )
    (net (code "20") (name "DAC3_O") (class "Default")
      (node (ref "C43") (pin "2") (pinfunction "2_2") (pintype "unspecified"))
      (node (ref "J29") (pin "2") (pinfunction "2_2") (pintype "unspecified"))
      (node (ref "J5") (pin "7") (pinfunction "7_7") (pintype "input"))
      (node (ref "J5") (pin "9") (pinfunction "9_9") (pintype "input"))
      (node (ref "R42") (pin "2") (pinfunction "2_2") (pintype "unspecified"))
      (node (ref "RF1") (pin "5") (pinfunction "5_5") (pintype "unspecified"))
    )
    (net (code "21") (name "DGND") (class "Default")
      (node (ref "C50") (pin "1") (pinfunction "1_1") (pintype "unspecified"))
      (node (ref "R6") (pin "2") (pinfunction "2_2") (pintype "unspecified"))
      (node (ref "U19") (pin "33") (pinfunction "DGND_33") (pintype "unspecified"))
    )
    (net (code "22") (name "DGND2") (class "Default")
      (node (ref "R7") (pin "2") (pinfunction "2_2") (pintype "unspecified"))
      (node (ref "U18") (pin "7") (pinfunction "DGND_7") (pintype "unspecified"))
    )
    (net (code "23") (name "GND") (class "Default")
      (node (ref "C1") (pin "1") (pinfunction "1_1") (pintype "unspecified"))
      (node (ref "C10") (pin "1") (pinfunction "1_1") (pintype "unspecified"))
      (node (ref "C13") (pin "1") (pinfunction "1_1") (pintype "unspecified"))
      (node (ref "C2") (pin "1") (pinfunction "1_1") (pintype "unspecified"))
      (node (ref "C3") (pin "1") (pinfunction "1_1") (pintype "unspecified"))
      (node (ref "C32") (pin "1") (pinfunction "1_1") (pintype "unspecified"))
      (node (ref "C33") (pin "1") (pinfunction "1_1") (pintype "unspecified"))
      (node (ref "C39") (pin "1") (pinfunction "1_1") (pintype "unspecified"))
      (node (ref "C4") (pin "1") (pinfunction "1_1") (pintype "unspecified"))
      (node (ref "C40") (pin "1") (pinfunction "1_1") (pintype "unspecified"))
      (node (ref "C41") (pin "1") (pinfunction "1_1") (pintype "unspecified"))
      (node (ref "C42") (pin "2") (pinfunction "2_2") (pintype "unspecified"))
      (node (ref "C43") (pin "1") (pinfunction "1_1") (pintype "unspecified"))
      (node (ref "C44") (pin "1") (pinfunction "1_1") (pintype "unspecified"))
      (node (ref "C45") (pin "2") (pinfunction "2_2") (pintype "unspecified"))
      (node (ref "C46") (pin "2") (pinfunction "2_2") (pintype "unspecified"))
      (node (ref "C47") (pin "2") (pinfunction "2_2") (pintype "unspecified"))
      (node (ref "C49") (pin "1") (pinfunction "1_1") (pintype "unspecified"))
      (node (ref "C5") (pin "1") (pinfunction "1_1") (pintype "unspecified"))
      (node (ref "C51") (pin "1") (pinfunction "1_1") (pintype "unspecified"))
      (node (ref "C7") (pin "1") (pinfunction "1_1") (pintype "unspecified"))
      (node (ref "H1") (pin "1") (pinfunction "1_1") (pintype "input"))
      (node (ref "H1") (pin "2") (pinfunction "2_2") (pintype "input"))
      (node (ref "H3") (pin "8") (pinfunction "8_8") (pintype "input"))
      (node (ref "J10") (pin "7") (pinfunction "7_7") (pintype "unspecified"))
      (node (ref "J11") (pin "2") (pinfunction "2_2") (pintype "unspecified"))
      (node (ref "J14") (pin "6") (pinfunction "6_6") (pintype "unspecified"))
      (node (ref "J14") (pin "7") (pinfunction "7_7") (pintype "unspecified"))
      (node (ref "J18") (pin "2") (pinfunction "2_2") (pintype "unspecified"))
      (node (ref "J24") (pin "3") (pinfunction "3_3") (pintype "input"))
      (node (ref "J25") (pin "3") (pinfunction "3_3") (pintype "input"))
      (node (ref "J29") (pin "1") (pinfunction "1_1") (pintype "unspecified"))
      (node (ref "J3") (pin "1") (pinfunction "1_1") (pintype "input"))
      (node (ref "J36") (pin "2") (pinfunction "2_2") (pintype "unspecified"))
      (node (ref "J37") (pin "2") (pinfunction "2_2") (pintype "unspecified"))
      (node (ref "J38") (pin "2") (pinfunction "2_2") (pintype "unspecified"))
      (node (ref "J7") (pin "5") (pinfunction "5_5") (pintype "input"))
      (node (ref "J7") (pin "6") (pinfunction "6_6") (pintype "input"))
      (node (ref "J8") (pin "1") (pinfunction "1_1") (pintype "input"))
      (node (ref "J8") (pin "2") (pinfunction "2_2") (pintype "input"))
      (node (ref "R44") (pin "1") (pinfunction "1_1") (pintype "unspecified"))
      (node (ref "R45") (pin "1") (pinfunction "1_1") (pintype "unspecified"))
      (node (ref "R47") (pin "1") (pinfunction "1_1") (pintype "unspecified"))
      (node (ref "R6") (pin "1") (pinfunction "1_1") (pintype "unspecified"))
      (node (ref "R7") (pin "1") (pinfunction "1_1") (pintype "unspecified"))
      (node (ref "RF1") (pin "1") (pinfunction "1_1") (pintype "unspecified"))
      (node (ref "RF1") (pin "2") (pinfunction "2_2") (pintype "unspecified"))
      (node (ref "RF1") (pin "3") (pinfunction "3_3") (pintype "unspecified"))
      (node (ref "RF1") (pin "4") (pinfunction "4_4") (pintype "unspecified"))
      (node (ref "RF2") (pin "1") (pinfunction "1_1") (pintype "unspecified"))
      (node (ref "RF2") (pin "2") (pinfunction "2_2") (pintype "unspecified"))
      (node (ref "RF2") (pin "3") (pinfunction "3_3") (pintype "unspecified"))
      (node (ref "RF2") (pin "4") (pinfunction "4_4") (pintype "unspecified"))
      (node (ref "RF3") (pin "1") (pinfunction "1_1") (pintype "unspecified"))
      (node (ref "RF3") (pin "2") (pinfunction "2_2") (pintype "unspecified"))
      (node (ref "RF3") (pin "3") (pinfunction "3_3") (pintype "unspecified"))
      (node (ref "RF3") (pin "4") (pinfunction "4_4") (pintype "unspecified"))
      (node (ref "RF4") (pin "1") (pinfunction "1_1") (pintype "unspecified"))
      (node (ref "RF4") (pin "2") (pinfunction "2_2") (pintype "unspecified"))
      (node (ref "RF4") (pin "3") (pinfunction "3_3") (pintype "unspecified"))
      (node (ref "RF4") (pin "4") (pinfunction "4_4") (pintype "unspecified"))
      (node (ref "U1") (pin "2") (pinfunction "1IN-_2") (pintype "unspecified"))
      (node (ref "U1") (pin "3") (pinfunction "1IN+_3") (pintype "unspecified"))
      (node (ref "U14") (pin "3") (pinfunction "3_3") (pintype "unspecified"))
      (node (ref "U16") (pin "2") (pinfunction "VSS_2") (pintype "unspecified"))
      (node (ref "U16") (pin "6") (pinfunction "A0_6") (pintype "unspecified"))
      (node (ref "U18") (pin "2") (pinfunction "AGND_2") (pintype "unspecified"))
      (node (ref "U19") (pin "28") (pinfunction "AGND_28") (pintype "unspecified"))
      (node (ref "U19") (pin "29") (pinfunction "AGND_29") (pintype "unspecified"))
      (node (ref "U19") (pin "3") (pinfunction "DAISY_3") (pintype "unspecified"))
      (node (ref "U19") (pin "31") (pinfunction "AGND_31") (pintype "unspecified"))
      (node (ref "U19") (pin "32") (pinfunction "AGND_32") (pintype "unspecified"))
      (node (ref "U19") (pin "4") (pinfunction "REFSEL#_4") (pintype "unspecified"))
      (node (ref "U19") (pin "6") (pinfunction "REFGND_6") (pintype "unspecified"))
      (node (ref "U19") (pin "8") (pinfunction "AGND_8") (pintype "unspecified"))
      (node (ref "U21") (pin "4") (pinfunction "GND_4") (pintype "unspecified"))
      (node (ref "U6") (pin "3") (pinfunction "3_3") (pintype "unspecified"))
      (node (ref "U8") (pin "3") (pinfunction "3_3") (pintype "unspecified"))
    )
    (net (code "24") (name "IN1") (class "Default")
      (node (ref "J25") (pin "1") (pinfunction "1_1") (pintype "input"))
      (node (ref "J5") (pin "8") (pinfunction "8_8") (pintype "input"))
      (node (ref "U12") (pin "3") (pinfunction "POS/A_3") (pintype "unspecified"))
      (node (ref "U8") (pin "1") (pinfunction "1_1") (pintype "unspecified"))
    )
    (net (code "25") (name "IN2") (class "Default")
      (node (ref "C27") (pin "1") (pinfunction "1_1") (pintype "unspecified"))
      (node (ref "C28") (pin "1") (pinfunction "1_1") (pintype "unspecified"))
      (node (ref "J25") (pin "2") (pinfunction "2_2") (pintype "input"))
      (node (ref "J5") (pin "12") (pinfunction "12_12") (pintype "input"))
      (node (ref "J5") (pin "4") (pinfunction "4_4") (pintype "input"))
      (node (ref "J5") (pin "6") (pinfunction "6_6") (pintype "input"))
      (node (ref "U8") (pin "2") (pinfunction "2_2") (pintype "unspecified"))
    )
    (net (code "26") (name "IN3") (class "Default")
      (node (ref "J24") (pin "1") (pinfunction "1_1") (pintype "input"))
      (node (ref "J5") (pin "10") (pinfunction "10_10") (pintype "input"))
      (node (ref "J5") (pin "14") (pinfunction "14_14") (pintype "input"))
      (node (ref "R29") (pin "2") (pinfunction "2_2") (pintype "unspecified"))
      (node (ref "R31") (pin "2") (pinfunction "2_2") (pintype "unspecified"))
      (node (ref "U14") (pin "1") (pinfunction "1_1") (pintype "unspecified"))
    )
    (net (code "27") (name "IN4") (class "Default")
      (node (ref "J24") (pin "2") (pinfunction "2_2") (pintype "input"))
      (node (ref "J5") (pin "2") (pinfunction "2_2") (pintype "input"))
      (node (ref "R36") (pin "2") (pinfunction "2_2") (pintype "unspecified"))
      (node (ref "R37") (pin "2") (pinfunction "2_2") (pintype "unspecified"))
      (node (ref "U14") (pin "2") (pinfunction "2_2") (pintype "unspecified"))
    )
    (net (code "28") (name "IOREF") (class "Default")
      (node (ref "J14") (pin "2") (pinfunction "2_2") (pintype "unspecified"))
    )
    (net (code "29") (name "MISO") (class "Default")
      (node (ref "H3") (pin "12") (pinfunction "12_12") (pintype "input"))
      (node (ref "J10") (pin "11") (pinfunction "11_11") (pintype "unspecified"))
    )
    (net (code "30") (name "MISO2") (class "Default")
      (node (ref "H3") (pin "19") (pinfunction "19_19") (pintype "input"))
      (node (ref "J10") (pin "20") (pinfunction "20_20") (pintype "unspecified"))
      (node (ref "U19") (pin "36") (pinfunction "SDO_36") (pintype "unspecified"))
    )
    (net (code "31") (name "MOSI") (class "Default")
      (node (ref "H3") (pin "14") (pinfunction "14_14") (pintype "input"))
      (node (ref "J10") (pin "13") (pinfunction "13_13") (pintype "unspecified"))
      (node (ref "U18") (pin "6") (pinfunction "SDI_6") (pintype "unspecified"))
    )
    (net (code "32") (name "MOSI2") (class "Default")
      (node (ref "H3") (pin "13") (pinfunction "13_13") (pintype "input"))
      (node (ref "J10") (pin "14") (pinfunction "14_14") (pintype "unspecified"))
      (node (ref "U19") (pin "1") (pinfunction "SDI_1") (pintype "unspecified"))
    )
    (net (code "33") (name "NRST") (class "Default")
      (node (ref "J14") (pin "3") (pinfunction "3_3") (pintype "unspecified"))
    )
    (net (code "34") (name "NSS") (class "Default")
      (node (ref "H3") (pin "16") (pinfunction "16_16") (pintype "input"))
      (node (ref "J10") (pin "15") (pinfunction "15_15") (pintype "unspecified"))
      (node (ref "U18") (pin "4") (pinfunction "CS#_4") (pintype "unspecified"))
    )
    (net (code "35") (name "NSS2") (class "Default")
      (node (ref "H3") (pin "17") (pinfunction "17_17") (pintype "input"))
      (node (ref "J10") (pin "18") (pinfunction "18_18") (pintype "unspecified"))
      (node (ref "U19") (pin "38") (pinfunction "CS#_38") (pintype "unspecified"))
    )
    (net (code "36") (name "Net-(C25-Pad2)") (class "Default")
      (node (ref "C25") (pin "2") (pinfunction "2_2") (pintype "unspecified"))
      (node (ref "J12") (pin "1") (pinfunction "1_1") (pintype "unspecified"))
    )
    (net (code "37") (name "Net-(C26-Pad2)") (class "Default")
      (node (ref "C26") (pin "2") (pinfunction "2_2") (pintype "unspecified"))
      (node (ref "C27") (pin "2") (pinfunction "2_2") (pintype "unspecified"))
      (node (ref "J12") (pin "2") (pinfunction "2_2") (pintype "unspecified"))
      (node (ref "J13") (pin "1") (pinfunction "1_1") (pintype "unspecified"))
      (node (ref "R28") (pin "2") (pinfunction "2_2") (pintype "unspecified"))
    )
    (net (code "38") (name "Net-(C28-Pad2)") (class "Default")
      (node (ref "C28") (pin "2") (pinfunction "2_2") (pintype "unspecified"))
      (node (ref "J13") (pin "2") (pinfunction "2_2") (pintype "unspecified"))
    )
    (net (code "39") (name "Net-(C31-Pad2)") (class "Default")
      (node (ref "C31") (pin "2") (pinfunction "2_2") (pintype "unspecified"))
      (node (ref "J4") (pin "1") (pinfunction "1_1") (pintype "unspecified"))
      (node (ref "J6") (pin "2") (pinfunction "2_2") (pintype "unspecified"))
      (node (ref "R34") (pin "2") (pinfunction "2_2") (pintype "unspecified"))
      (node (ref "R36") (pin "1") (pinfunction "1_1") (pintype "unspecified"))
    )
    (net (code "40") (name "Net-(C34-Pad2)") (class "Default")
      (node (ref "C34") (pin "2") (pinfunction "2_2") (pintype "unspecified"))
      (node (ref "J1") (pin "1") (pinfunction "1_1") (pintype "unspecified"))
      (node (ref "J2") (pin "2") (pinfunction "2_2") (pintype "unspecified"))
      (node (ref "R31") (pin "1") (pinfunction "1_1") (pintype "unspecified"))
      (node (ref "R33") (pin "2") (pinfunction "2_2") (pintype "unspecified"))
    )
    (net (code "41") (name "Net-(J1-Pad2)") (class "Default")
      (node (ref "J1") (pin "2") (pinfunction "2_2") (pintype "unspecified"))
      (node (ref "R29") (pin "1") (pinfunction "1_1") (pintype "unspecified"))
    )
    (net (code "42") (name "Net-(J2-Pad1)") (class "Default")
      (node (ref "J2") (pin "1") (pinfunction "1_1") (pintype "unspecified"))
      (node (ref "R32") (pin "2") (pinfunction "2_2") (pintype "unspecified"))
    )
    (net (code "43") (name "Net-(J3-Pad2)") (class "Default")
      (node (ref "J3") (pin "2") (pinfunction "2_2") (pintype "input"))
      (node (ref "R27") (pin "1") (pinfunction "1_1") (pintype "unspecified"))
    )
    (net (code "44") (name "Net-(J4-Pad2)") (class "Default")
      (node (ref "J4") (pin "2") (pinfunction "2_2") (pintype "unspecified"))
      (node (ref "R35") (pin "2") (pinfunction "2_2") (pintype "unspecified"))
    )
    (net (code "45") (name "Net-(J6-Pad1)") (class "Default")
      (node (ref "J6") (pin "1") (pinfunction "1_1") (pintype "unspecified"))
      (node (ref "R37") (pin "1") (pinfunction "1_1") (pintype "unspecified"))
    )
    (net (code "46") (name "Net-(J18-Pad1)") (class "Default")
      (node (ref "J18") (pin "1") (pinfunction "1_1") (pintype "unspecified"))
      (node (ref "R30") (pin "1") (pinfunction "1_1") (pintype "unspecified"))
    )
    (net (code "47") (name "Net-(J36-Pad1)") (class "Default")
      (node (ref "J36") (pin "1") (pinfunction "1_1") (pintype "unspecified"))
      (node (ref "R43") (pin "1") (pinfunction "1_1") (pintype "unspecified"))
      (node (ref "RF2") (pin "5") (pinfunction "5_5") (pintype "unspecified"))
    )
    (net (code "48") (name "Net-(J37-Pad1)") (class "Default")
      (node (ref "J37") (pin "1") (pinfunction "1_1") (pintype "unspecified"))
      (node (ref "R46") (pin "1") (pinfunction "1_1") (pintype "unspecified"))
      (node (ref "RF3") (pin "5") (pinfunction "5_5") (pintype "unspecified"))
    )
    (net (code "49") (name "Net-(J38-Pad1)") (class "Default")
      (node (ref "J38") (pin "1") (pinfunction "1_1") (pintype "unspecified"))
      (node (ref "R48") (pin "1") (pinfunction "1_1") (pintype "unspecified"))
      (node (ref "RF4") (pin "5") (pinfunction "5_5") (pintype "unspecified"))
    )
    (net (code "50") (name "Net-(U4-POS{slash}A)") (class "Default")
      (node (ref "C33") (pin "2") (pinfunction "2_2") (pintype "unspecified"))
      (node (ref "R32") (pin "1") (pinfunction "1_1") (pintype "unspecified"))
      (node (ref "R33") (pin "1") (pinfunction "1_1") (pintype "unspecified"))
      (node (ref "U4") (pin "3") (pinfunction "POS/A_3") (pintype "unspecified"))
    )
    (net (code "51") (name "Net-(U4-POS{slash}B)") (class "Default")
      (node (ref "C32") (pin "2") (pinfunction "2_2") (pintype "unspecified"))
      (node (ref "R34") (pin "1") (pinfunction "1_1") (pintype "unspecified"))
      (node (ref "R35") (pin "1") (pinfunction "1_1") (pintype "unspecified"))
      (node (ref "U4") (pin "5") (pinfunction "POS/B_5") (pintype "unspecified"))
    )
    (net (code "52") (name "Net-(U12-NEG{slash}A)") (class "Default")
      (node (ref "C38") (pin "1") (pinfunction "1_1") (pintype "unspecified"))
      (node (ref "R26") (pin "1") (pinfunction "1_1") (pintype "unspecified"))
      (node (ref "R30") (pin "2") (pinfunction "2_2") (pintype "unspecified"))
      (node (ref "U12") (pin "2") (pinfunction "NEG/A_2") (pintype "unspecified"))
    )
    (net (code "53") (name "Net-(U12-POS{slash}B)") (class "Default")
      (node (ref "C25") (pin "1") (pinfunction "1_1") (pintype "unspecified"))
      (node (ref "C26") (pin "1") (pinfunction "1_1") (pintype "unspecified"))
      (node (ref "R27") (pin "2") (pinfunction "2_2") (pintype "unspecified"))
      (node (ref "U12") (pin "5") (pinfunction "POS/B_5") (pintype "unspecified"))
    )
    (net (code "54") (name "Net-(U18-VDD)") (class "Default")
      (node (ref "C42") (pin "1") (pinfunction "1_1") (pintype "unspecified"))
      (node (ref "R4") (pin "2") (pinfunction "2_2") (pintype "unspecified"))
      (node (ref "U18") (pin "8") (pinfunction "VDD_8") (pintype "unspecified"))
    )
    (net (code "55") (name "Net-(U18-VOUT)") (class "Default")
      (node (ref "R42") (pin "1") (pinfunction "1_1") (pintype "unspecified"))
      (node (ref "U18") (pin "1") (pinfunction "VOUT_1") (pintype "unspecified"))
    )
    (net (code "56") (name "Net-(U21-VIN)") (class "Default")
      (node (ref "C41") (pin "2") (pinfunction "2_2") (pintype "unspecified"))
      (node (ref "R5") (pin "2") (pinfunction "2_2") (pintype "unspecified"))
      (node (ref "U21") (pin "2") (pinfunction "VIN_2") (pintype "unspecified"))
    )
    (net (code "57") (name "Net-(U21-VOUT)") (class "Default")
      (node (ref "R3") (pin "1") (pinfunction "1_1") (pintype "unspecified"))
      (node (ref "U21") (pin "6") (pinfunction "VOUT_6") (pintype "unspecified"))
    )
    (net (code "58") (name "OUT1") (class "Default")
      (node (ref "C38") (pin "2") (pinfunction "2_2") (pintype "unspecified"))
      (node (ref "J5") (pin "11") (pinfunction "11_11") (pintype "input"))
      (node (ref "J5") (pin "13") (pinfunction "13_13") (pintype "input"))
      (node (ref "J7") (pin "1") (pinfunction "1_1") (pintype "input"))
      (node (ref "R26") (pin "2") (pinfunction "2_2") (pintype "unspecified"))
      (node (ref "U12") (pin "1") (pinfunction "OUT/A_1") (pintype "unspecified"))
    )
    (net (code "59") (name "OUT2") (class "Default")
      (node (ref "J7") (pin "2") (pinfunction "2_2") (pintype "input"))
      (node (ref "R28") (pin "1") (pinfunction "1_1") (pintype "unspecified"))
      (node (ref "U12") (pin "6") (pinfunction "NEG/B_6") (pintype "unspecified"))
      (node (ref "U12") (pin "7") (pinfunction "OUT/B_7") (pintype "unspecified"))
    )
    (net (code "60") (name "OUT3") (class "Default")
      (node (ref "C34") (pin "1") (pinfunction "1_1") (pintype "unspecified"))
      (node (ref "J5") (pin "1") (pinfunction "1_1") (pintype "input"))
      (node (ref "J5") (pin "3") (pinfunction "3_3") (pintype "input"))
      (node (ref "J7") (pin "3") (pinfunction "3_3") (pintype "input"))
      (node (ref "U4") (pin "1") (pinfunction "OUT/A_1") (pintype "unspecified"))
      (node (ref "U4") (pin "2") (pinfunction "NEG/A_2") (pintype "unspecified"))
    )
    (net (code "61") (name "OUT4") (class "Default")
      (node (ref "C31") (pin "1") (pinfunction "1_1") (pintype "unspecified"))
      (node (ref "J5") (pin "5") (pinfunction "5_5") (pintype "input"))
      (node (ref "J7") (pin "4") (pinfunction "4_4") (pintype "input"))
      (node (ref "U4") (pin "6") (pinfunction "NEG/B_6") (pintype "unspecified"))
      (node (ref "U4") (pin "7") (pinfunction "OUT/B_7") (pintype "unspecified"))
    )
    (net (code "62") (name "SCK") (class "Default")
      (node (ref "H3") (pin "10") (pinfunction "10_10") (pintype "input"))
      (node (ref "J10") (pin "9") (pinfunction "9_9") (pintype "unspecified"))
      (node (ref "U18") (pin "5") (pinfunction "SCLK_5") (pintype "unspecified"))
    )
    (net (code "63") (name "SCK2") (class "Default")
      (node (ref "H3") (pin "15") (pinfunction "15_15") (pintype "input"))
      (node (ref "J10") (pin "16") (pinfunction "16_16") (pintype "unspecified"))
      (node (ref "U19") (pin "37") (pinfunction "SCLK_37") (pintype "unspecified"))
    )
    (net (code "64") (name "SCL") (class "Default")
      (node (ref "H3") (pin "2") (pinfunction "2_2") (pintype "input"))
      (node (ref "J10") (pin "1") (pinfunction "1_1") (pintype "unspecified"))
      (node (ref "U16") (pin "5") (pinfunction "SCL_5") (pintype "unspecified"))
    )
    (net (code "65") (name "SDA") (class "Default")
      (node (ref "H3") (pin "4") (pinfunction "4_4") (pintype "input"))
      (node (ref "J10") (pin "3") (pinfunction "3_3") (pintype "unspecified"))
      (node (ref "U16") (pin "4") (pinfunction "SDA_4") (pintype "unspecified"))
    )
    (net (code "66") (name "VCC") (class "Default")
      (node (ref "C10") (pin "2") (pinfunction "2_2") (pintype "unspecified"))
      (node (ref "C13") (pin "2") (pinfunction "2_2") (pintype "unspecified"))
      (node (ref "R1") (pin "1") (pinfunction "1_1") (pintype "unspecified"))
      (node (ref "R38") (pin "2") (pinfunction "2_2") (pintype "unspecified"))
    )
    (net (code "67") (name "VCC1") (class "Default")
      (node (ref "C3") (pin "2") (pinfunction "2_2") (pintype "unspecified"))
      (node (ref "R1") (pin "2") (pinfunction "2_2") (pintype "unspecified"))
      (node (ref "U1") (pin "8") (pinfunction "VCC_8") (pintype "unspecified"))
      (node (ref "U12") (pin "8") (pinfunction "V+_8") (pintype "unspecified"))
      (node (ref "U4") (pin "8") (pinfunction "V+_8") (pintype "unspecified"))
    )
    (net (code "68") (name "VCC_I") (class "Default")
      (node (ref "R38") (pin "1") (pinfunction "1_1") (pintype "unspecified"))
      (node (ref "U6") (pin "1") (pinfunction "1_1") (pintype "unspecified"))
    )
    (net (code "69") (name "VCM") (class "Default")
      (node (ref "J3") (pin "3") (pinfunction "3_3") (pintype "input"))
      (node (ref "U1") (pin "6") (pinfunction "2IN-_6") (pintype "unspecified"))
      (node (ref "U1") (pin "7") (pinfunction "2OUT_7") (pintype "unspecified"))
    )
    (net (code "70") (name "VEE") (class "Default")
      (node (ref "C1") (pin "2") (pinfunction "2_2") (pintype "unspecified"))
      (node (ref "C2") (pin "2") (pinfunction "2_2") (pintype "unspecified"))
      (node (ref "R2") (pin "1") (pinfunction "1_1") (pintype "unspecified"))
      (node (ref "R39") (pin "2") (pinfunction "2_2") (pintype "unspecified"))
    )
    (net (code "71") (name "VEE1") (class "Default")
      (node (ref "C4") (pin "2") (pinfunction "2_2") (pintype "unspecified"))
      (node (ref "R2") (pin "2") (pinfunction "2_2") (pintype "unspecified"))
      (node (ref "U1") (pin "4") (pinfunction "GND_4") (pintype "unspecified"))
      (node (ref "U12") (pin "4") (pinfunction "V-_4") (pintype "unspecified"))
      (node (ref "U4") (pin "4") (pinfunction "V-_4") (pintype "unspecified"))
    )
    (net (code "72") (name "VEE_I") (class "Default")
      (node (ref "R39") (pin "1") (pinfunction "1_1") (pintype "unspecified"))
      (node (ref "U6") (pin "2") (pinfunction "2_2") (pintype "unspecified"))
    )
    (net (code "73") (name "VIN") (class "Default")
      (node (ref "J14") (pin "8") (pinfunction "8_8") (pintype "unspecified"))
    )
    (net (code "74") (name "VREF") (class "Default")
      (node (ref "C39") (pin "2") (pinfunction "2_2") (pintype "unspecified"))
      (node (ref "C40") (pin "2") (pinfunction "2_2") (pintype "unspecified"))
      (node (ref "J9") (pin "1") (pinfunction "1_1") (pintype "input"))
      (node (ref "R3") (pin "2") (pinfunction "2_2") (pintype "unspecified"))
      (node (ref "U18") (pin "3") (pinfunction "VREF_3") (pintype "unspecified"))
    )
    (net (code "75") (name "VREFCAP") (class "Default")
      (node (ref "C44") (pin "2") (pinfunction "2_2") (pintype "unspecified"))
      (node (ref "C45") (pin "1") (pinfunction "1_1") (pintype "unspecified"))
      (node (ref "U19") (pin "7") (pinfunction "REFCAP_7") (pintype "unspecified"))
    )
    (net (code "76") (name "VREFIO") (class "Default")
      (node (ref "C49") (pin "2") (pinfunction "2_2") (pintype "unspecified"))
      (node (ref "U19") (pin "5") (pinfunction "REFIO_5") (pintype "unspecified"))
    )
    (net (code "77") (name "unconnected-(J14-Pad1)") (class "Default")
      (node (ref "J14") (pin "1") (pinfunction "1_1") (pintype "unspecified"))
    )
    (net (code "78") (name "unconnected-(U1-1OUT-Pad1)") (class "Default")
      (node (ref "U1") (pin "1") (pinfunction "1OUT_1") (pintype "unspecified"))
    )
    (net (code "79") (name "unconnected-(U19-AIN2_GND-Pad20)") (class "Default")
      (node (ref "U19") (pin "20") (pinfunction "AIN2_GND_20") (pintype "unspecified"))
    )
    (net (code "80") (name "unconnected-(U19-AIN_2P-Pad21)") (class "Default")
      (node (ref "U19") (pin "21") (pinfunction "AIN_2P_21") (pintype "unspecified"))
    )
    (net (code "81") (name "unconnected-(U19-AIN_3GND-Pad22)") (class "Default")
      (node (ref "U19") (pin "22") (pinfunction "AIN_3GND_22") (pintype "unspecified"))
    )
    (net (code "82") (name "unconnected-(U19-AIN_3P-Pad23)") (class "Default")
      (node (ref "U19") (pin "23") (pinfunction "AIN_3P_23") (pintype "unspecified"))
    )
    (net (code "83") (name "unconnected-(U19-AIN_4GND-Pad24)") (class "Default")
      (node (ref "U19") (pin "24") (pinfunction "AIN_4GND_24") (pintype "unspecified"))
    )
    (net (code "84") (name "unconnected-(U19-AIN_4P-Pad25)") (class "Default")
      (node (ref "U19") (pin "25") (pinfunction "AIN_4P_25") (pintype "unspecified"))
    )
    (net (code "85") (name "unconnected-(U19-AIN_5GND-Pad26)") (class "Default")
      (node (ref "U19") (pin "26") (pinfunction "AIN_5GND_26") (pintype "unspecified"))
    )
    (net (code "86") (name "unconnected-(U19-AIN_5P-Pad27)") (class "Default")
      (node (ref "U19") (pin "27") (pinfunction "AIN_5P_27") (pintype "unspecified"))
    )
    (net (code "87") (name "unconnected-(U19-AIN_6GND-Pad13)") (class "Default")
      (node (ref "U19") (pin "13") (pinfunction "AIN_6GND_13") (pintype "unspecified"))
    )
    (net (code "88") (name "unconnected-(U19-AIN_6P-Pad12)") (class "Default")
      (node (ref "U19") (pin "12") (pinfunction "AIN_6P_12") (pintype "unspecified"))
    )
    (net (code "89") (name "unconnected-(U19-AIN_7GND-Pad15)") (class "Default")
      (node (ref "U19") (pin "15") (pinfunction "AIN_7GND_15") (pintype "unspecified"))
    )
    (net (code "90") (name "unconnected-(U19-AIN_7P-Pad14)") (class "Default")
      (node (ref "U19") (pin "14") (pinfunction "AIN_7P_14") (pintype "unspecified"))
    )
    (net (code "91") (name "unconnected-(U19-DNC-Pad35)") (class "Default")
      (node (ref "U19") (pin "35") (pinfunction "DNC_35") (pintype "unspecified"))
    )
    (net (code "92") (name "unconnected-(U21-DNC-Pad1)") (class "Default")
      (node (ref "U21") (pin "1") (pinfunction "DNC_1") (pintype "unspecified"))
    )
    (net (code "93") (name "unconnected-(U21-DNC-Pad8)") (class "Default")
      (node (ref "U21") (pin "8") (pinfunction "DNC_8") (pintype "unspecified"))
    )
    (net (code "94") (name "unconnected-(U21-NC-Pad7)") (class "Default")
      (node (ref "U21") (pin "7") (pinfunction "NC_7") (pintype "unspecified"))
    )
    (net (code "95") (name "unconnected-(U21-TEMP-Pad3)") (class "Default")
      (node (ref "U21") (pin "3") (pinfunction "TEMP_3") (pintype "unspecified"))
    )
    (net (code "96") (name "unconnected-(U21-TRIM{slash}NR-Pad5)") (class "Default")
      (node (ref "U21") (pin "5") (pinfunction "TRIM/NR_5") (pintype "unspecified"))
    )
  )
)
